# glassesBoard.net
KiCad netlist of a schematic drawn in EAGLE
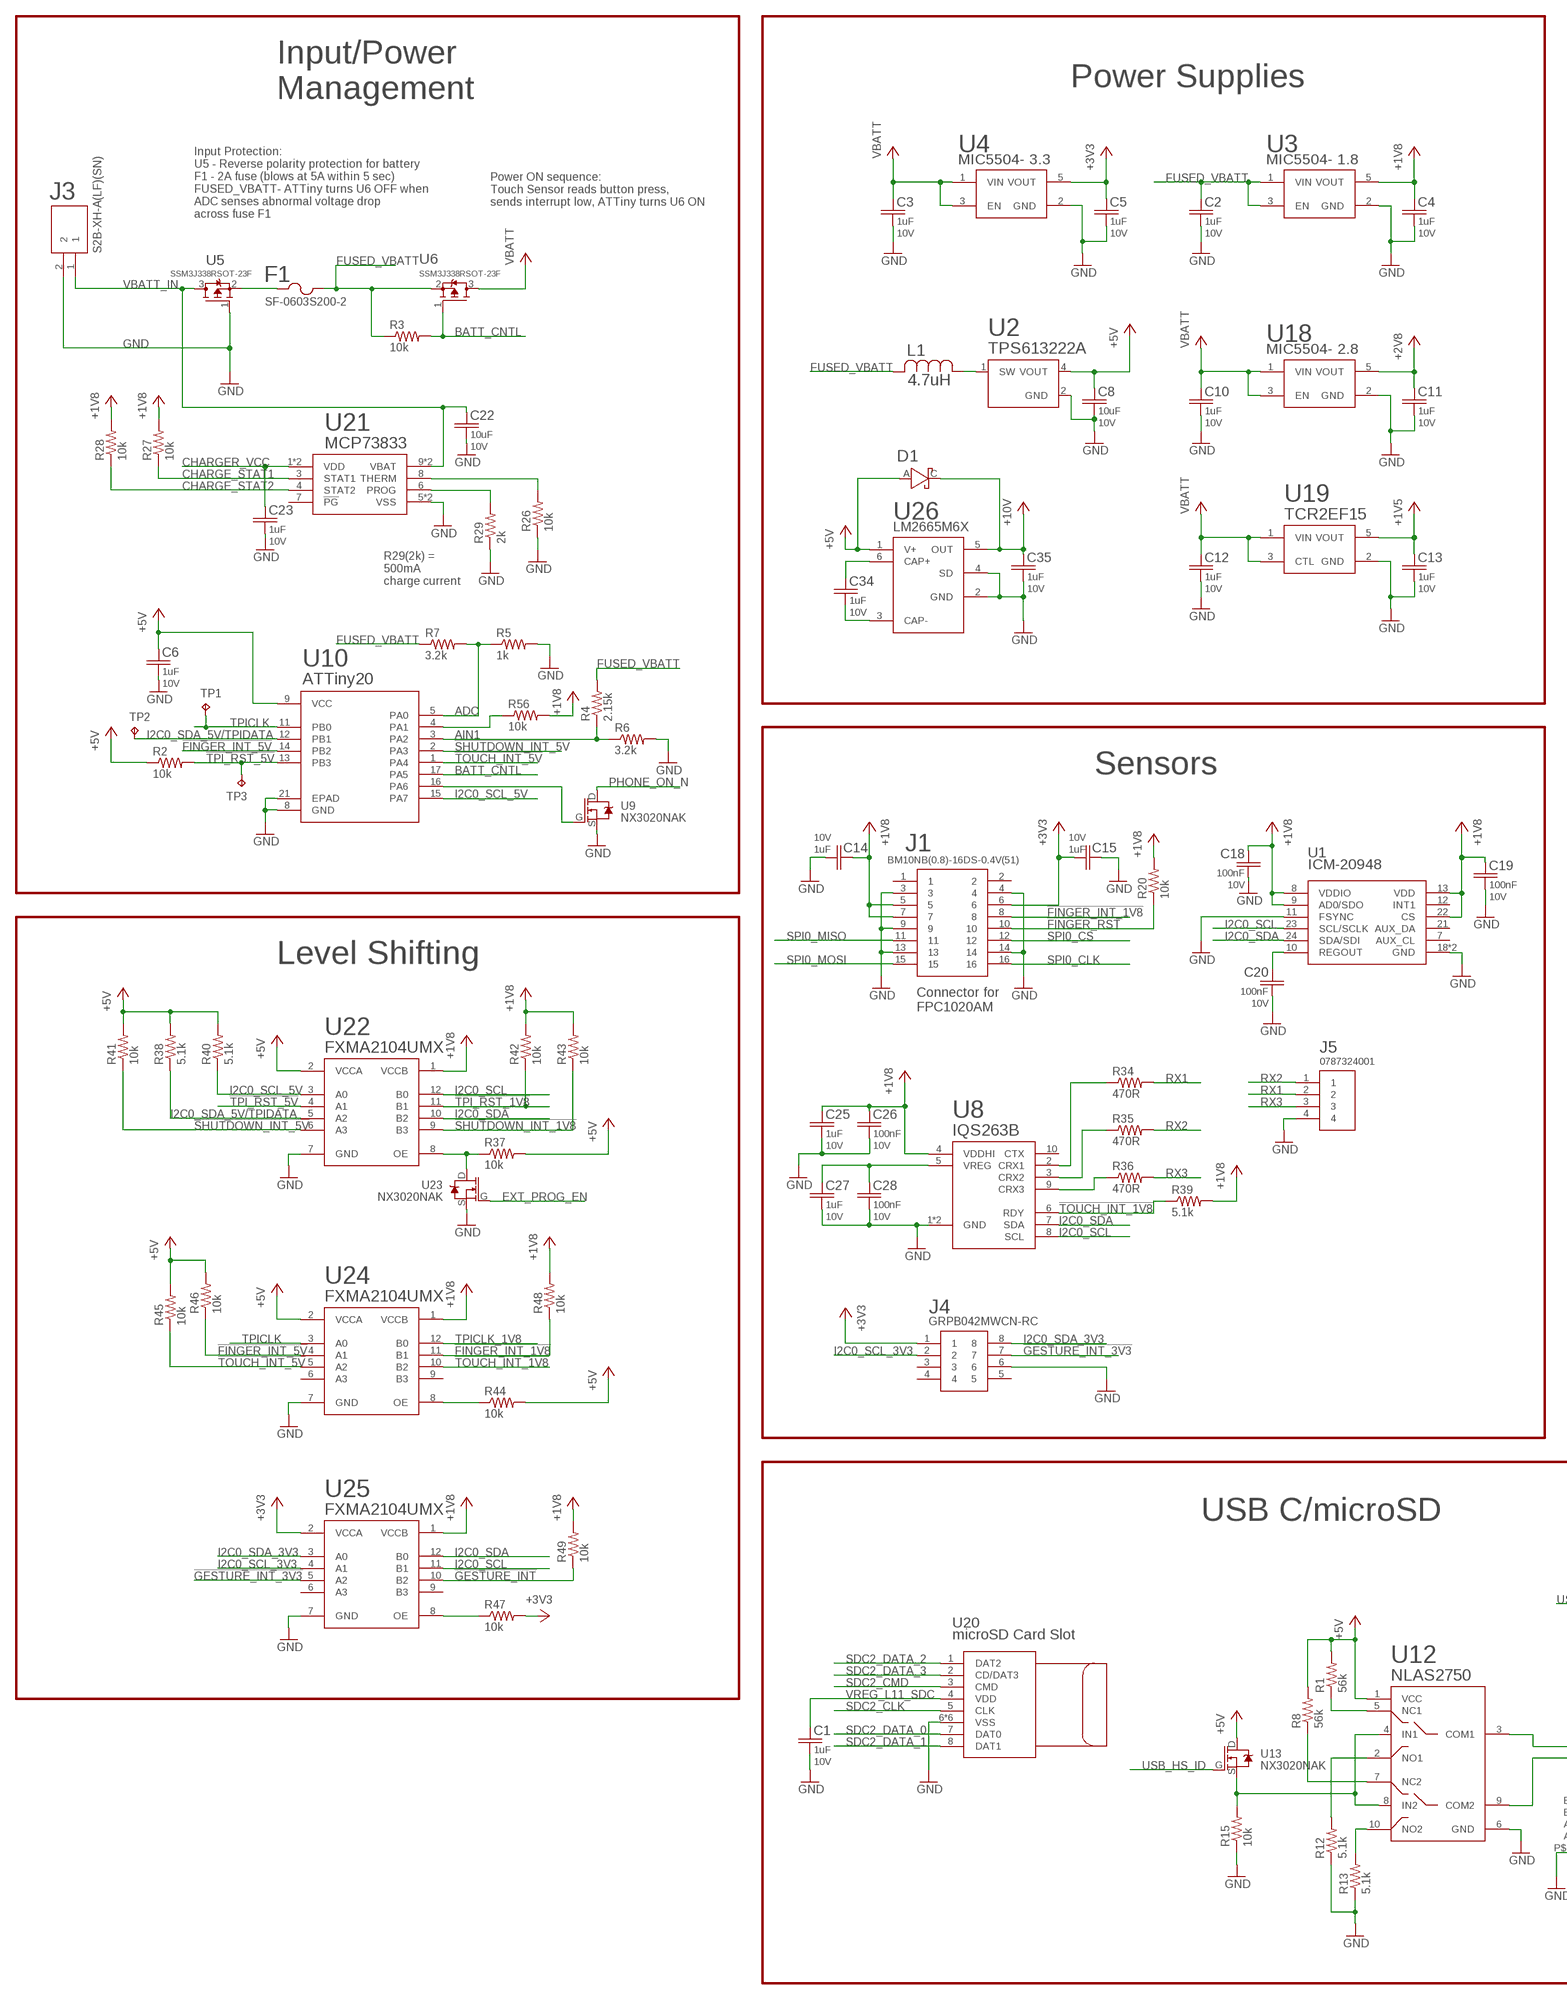
[diagram p0: schematic, sheet 1, part 1 of 2]
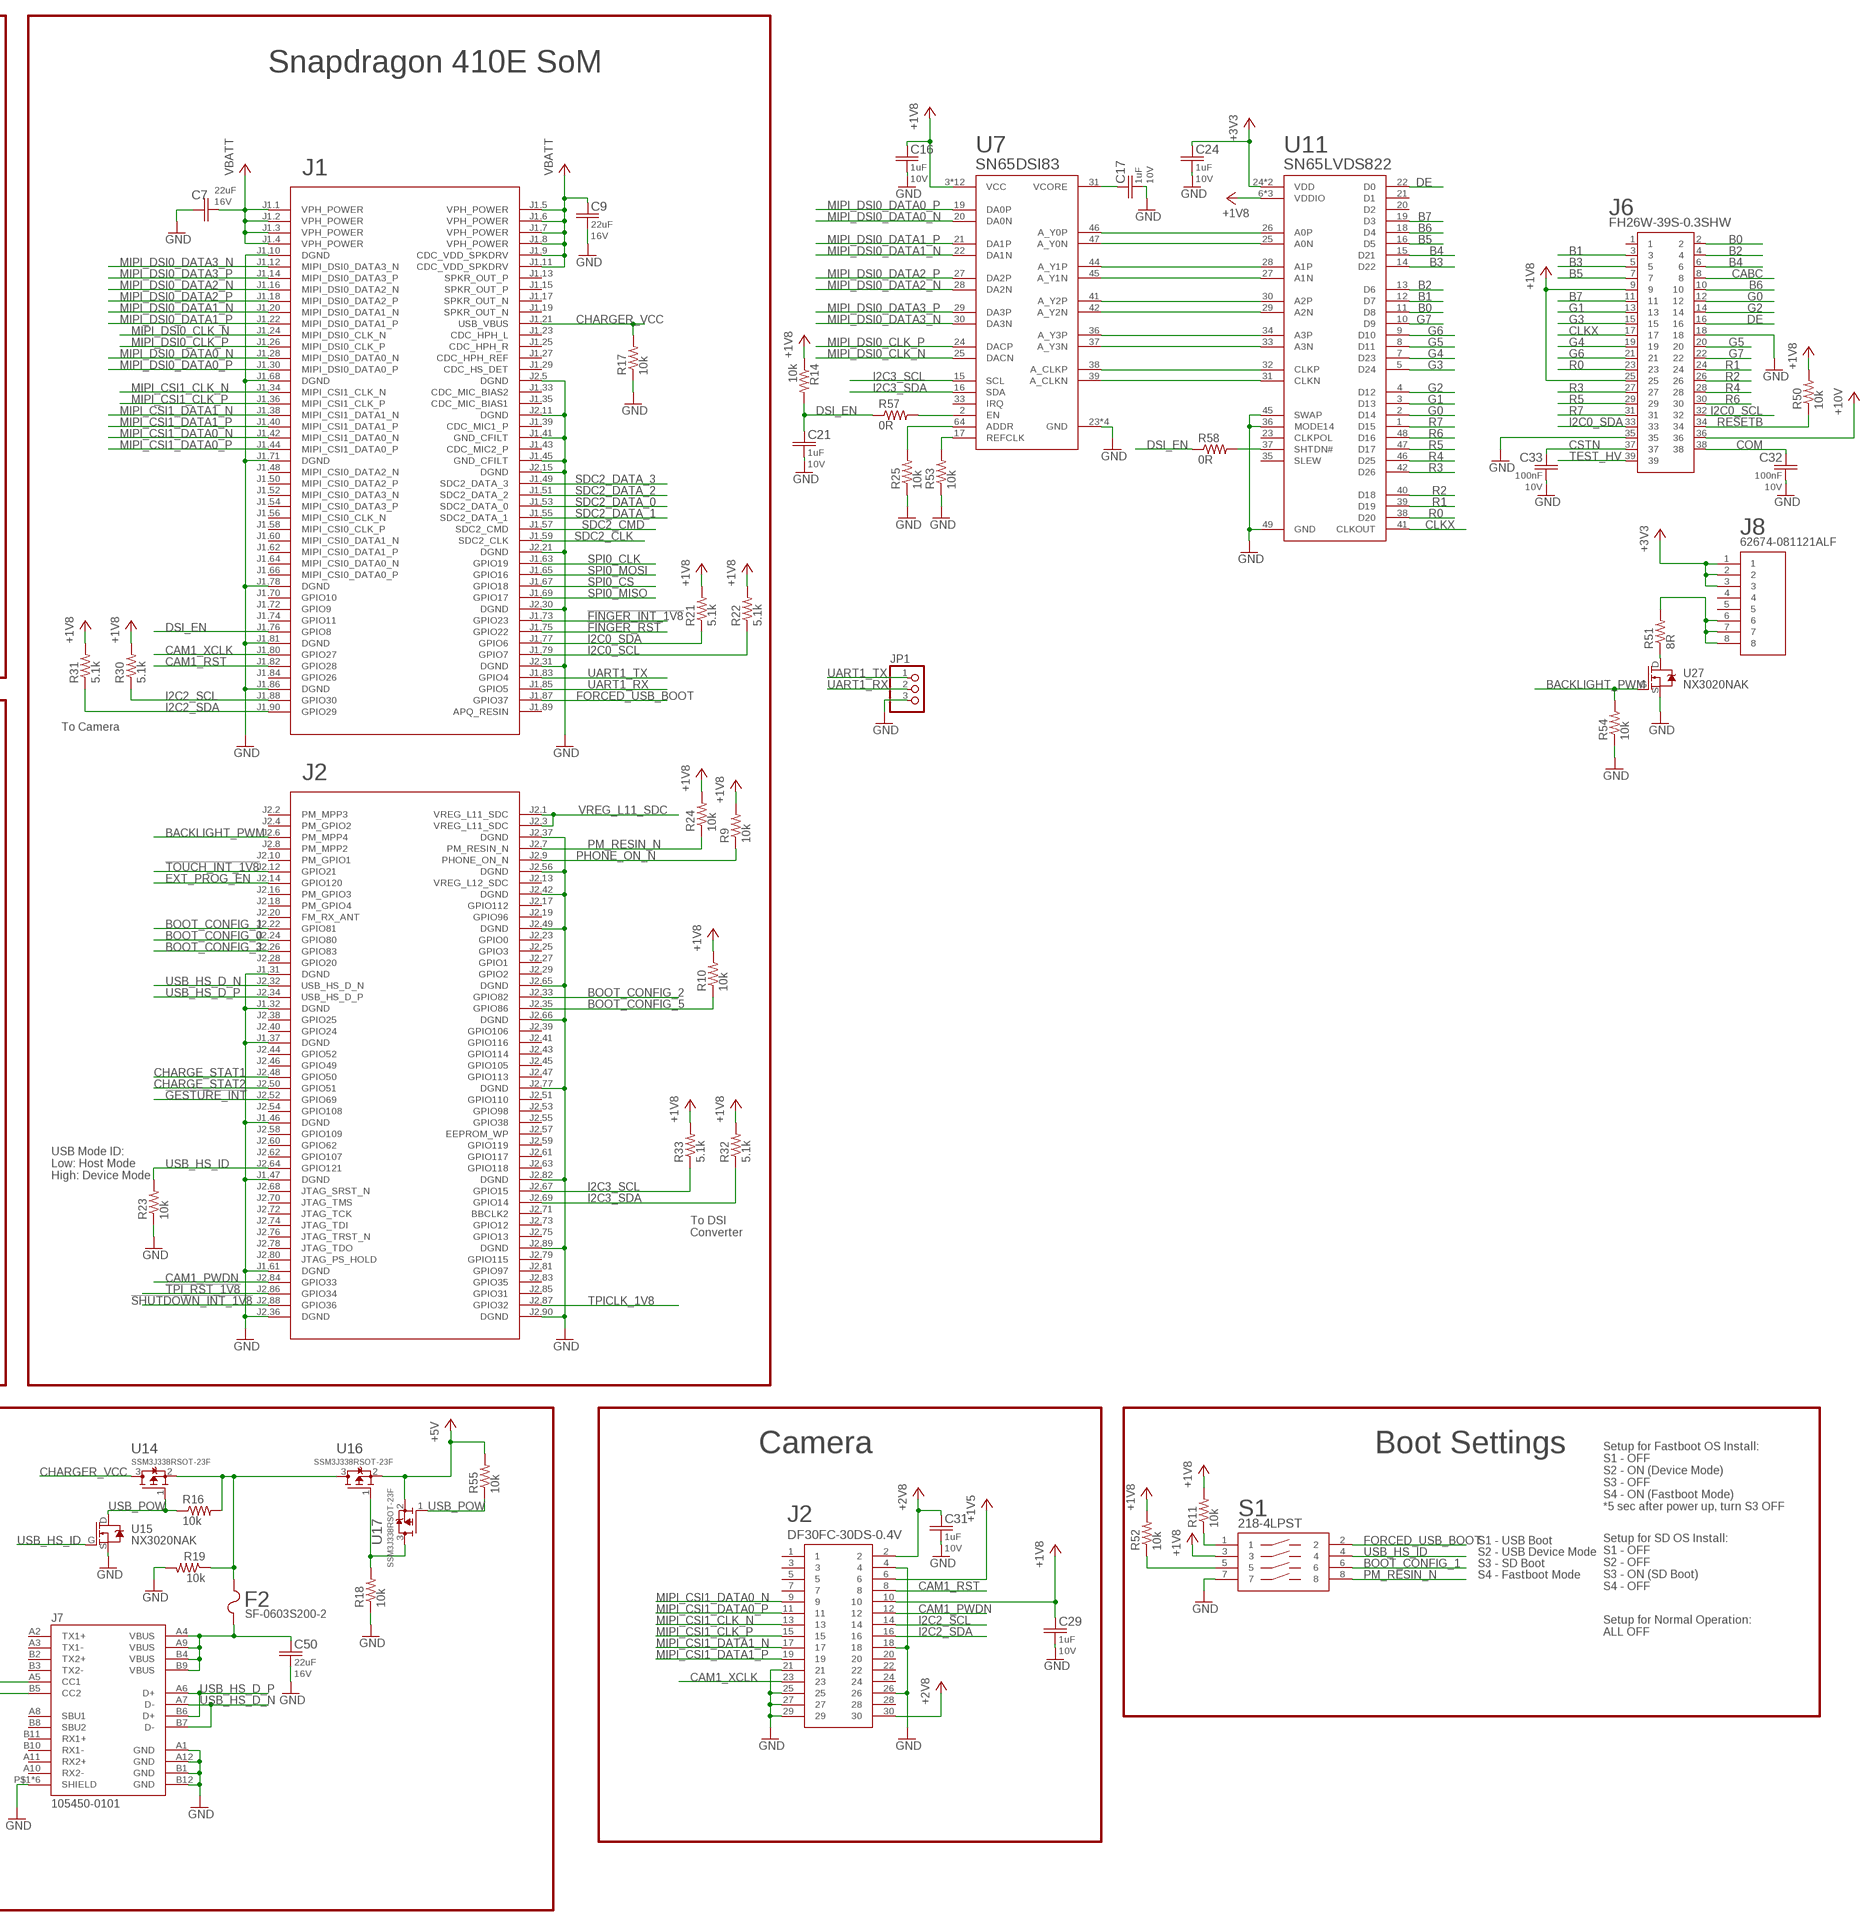
[diagram p1: schematic, sheet 1, part 2 of 2]

(export (version "E")
  (design (tool "Eeschema 10.0.6"))
  (components
    (comp (ref "C1")
      (value "1uF")
      (footprint "eagle-import:C0402")
      (fields (field (name "RATING") "10V"))
      (libsource (lib "eagle-import") (part "CL05A105MP5NNNC"))
    )
    (comp (ref "C2")
      (value "1uF")
      (footprint "eagle-import:C0402")
      (fields (field (name "RATING") "10V"))
      (libsource (lib "eagle-import") (part "CL05A105MP5NNNC"))
    )
    (comp (ref "C3")
      (value "1uF")
      (footprint "eagle-import:C0402")
      (fields (field (name "RATING") "10V"))
      (libsource (lib "eagle-import") (part "CL05A105MP5NNNC"))
    )
    (comp (ref "C4")
      (value "1uF")
      (footprint "eagle-import:C0402")
      (fields (field (name "RATING") "10V"))
      (libsource (lib "eagle-import") (part "CL05A105MP5NNNC"))
    )
    (comp (ref "C5")
      (value "1uF")
      (footprint "eagle-import:C0402")
      (fields (field (name "RATING") "10V"))
      (libsource (lib "eagle-import") (part "CL05A105MP5NNNC"))
    )
    (comp (ref "C6")
      (value "1uF")
      (footprint "eagle-import:C0402")
      (fields (field (name "RATING") "10V"))
      (libsource (lib "eagle-import") (part "CL05A105MP5NNNC"))
    )
    (comp (ref "C7")
      (value "22uF")
      (footprint "eagle-import:C0805")
      (fields (field (name "RATING") "16V"))
      (libsource (lib "eagle-import") (part "CL21A226MOCLRNC"))
    )
    (comp (ref "C8")
      (value "10uF")
      (footprint "eagle-import:C0603")
      (fields (field (name "RATING") "10V"))
      (libsource (lib "eagle-import") (part "GRM188R61A106KE69D"))
    )
    (comp (ref "C9")
      (value "22uF")
      (footprint "eagle-import:C0805")
      (fields (field (name "RATING") "16V"))
      (libsource (lib "eagle-import") (part "CL21A226MOCLRNC"))
    )
    (comp (ref "C10")
      (value "1uF")
      (footprint "eagle-import:C0402")
      (fields (field (name "RATING") "10V"))
      (libsource (lib "eagle-import") (part "CL05A105MP5NNNC"))
    )
    (comp (ref "C11")
      (value "1uF")
      (footprint "eagle-import:C0402")
      (fields (field (name "RATING") "10V"))
      (libsource (lib "eagle-import") (part "CL05A105MP5NNNC"))
    )
    (comp (ref "C12")
      (value "1uF")
      (footprint "eagle-import:C0402")
      (fields (field (name "RATING") "10V"))
      (libsource (lib "eagle-import") (part "CL05A105MP5NNNC"))
    )
    (comp (ref "C13")
      (value "1uF")
      (footprint "eagle-import:C0402")
      (fields (field (name "RATING") "10V"))
      (libsource (lib "eagle-import") (part "CL05A105MP5NNNC"))
    )
    (comp (ref "C14")
      (value "1uF")
      (footprint "eagle-import:C0402")
      (fields (field (name "RATING") "10V"))
      (libsource (lib "eagle-import") (part "CL05A105MP5NNNC"))
    )
    (comp (ref "C15")
      (value "1uF")
      (footprint "eagle-import:C0402")
      (fields (field (name "RATING") "10V"))
      (libsource (lib "eagle-import") (part "CL05A105MP5NNNC"))
    )
    (comp (ref "C16")
      (value "1uF")
      (footprint "eagle-import:C0402")
      (fields (field (name "RATING") "10V"))
      (libsource (lib "eagle-import") (part "CL05A105MP5NNNC"))
    )
    (comp (ref "C17")
      (value "1uF")
      (footprint "eagle-import:C0402")
      (fields (field (name "RATING") "10V"))
      (libsource (lib "eagle-import") (part "CL05A105MP5NNNC"))
    )
    (comp (ref "C18")
      (value "100nF")
      (footprint "eagle-import:C0402")
      (fields (field (name "RATING") "10V"))
      (libsource (lib "eagle-import") (part "CL05A104MP5NNNC"))
    )
    (comp (ref "C19")
      (value "100nF")
      (footprint "eagle-import:C0402")
      (fields (field (name "RATING") "10V"))
      (libsource (lib "eagle-import") (part "CL05A104MP5NNNC"))
    )
    (comp (ref "C20")
      (value "100nF")
      (footprint "eagle-import:C0402")
      (fields (field (name "RATING") "10V"))
      (libsource (lib "eagle-import") (part "CL05A104MP5NNNC"))
    )
    (comp (ref "C21")
      (value "1uF")
      (footprint "eagle-import:C0402")
      (fields (field (name "RATING") "10V"))
      (libsource (lib "eagle-import") (part "CL05A105MP5NNNC"))
    )
    (comp (ref "C22")
      (value "10uF")
      (footprint "eagle-import:C0603")
      (fields (field (name "RATING") "10V"))
      (libsource (lib "eagle-import") (part "GRM188R61A106KE69D"))
    )
    (comp (ref "C23")
      (value "1uF")
      (footprint "eagle-import:C0402")
      (fields (field (name "RATING") "10V"))
      (libsource (lib "eagle-import") (part "CL05A105MP5NNNC"))
    )
    (comp (ref "C24")
      (value "1uF")
      (footprint "eagle-import:C0402")
      (fields (field (name "RATING") "10V"))
      (libsource (lib "eagle-import") (part "CL05A105MP5NNNC"))
    )
    (comp (ref "C25")
      (value "1uF")
      (footprint "eagle-import:C0402")
      (fields (field (name "RATING") "10V"))
      (libsource (lib "eagle-import") (part "CL05A105MP5NNNC"))
    )
    (comp (ref "C26")
      (value "100nF")
      (footprint "eagle-import:C0402")
      (fields (field (name "RATING") "10V"))
      (libsource (lib "eagle-import") (part "CL05A104MP5NNNC"))
    )
    (comp (ref "C27")
      (value "1uF")
      (footprint "eagle-import:C0402")
      (fields (field (name "RATING") "10V"))
      (libsource (lib "eagle-import") (part "CL05A105MP5NNNC"))
    )
    (comp (ref "C28")
      (value "100nF")
      (footprint "eagle-import:C0402")
      (fields (field (name "RATING") "10V"))
      (libsource (lib "eagle-import") (part "CL05A104MP5NNNC"))
    )
    (comp (ref "C29")
      (value "1uF")
      (footprint "eagle-import:C0402")
      (fields (field (name "RATING") "10V"))
      (libsource (lib "eagle-import") (part "CL05A105MP5NNNC"))
    )
    (comp (ref "C31")
      (value "1uF")
      (footprint "eagle-import:C0402")
      (fields (field (name "RATING") "10V"))
      (libsource (lib "eagle-import") (part "CL05A105MP5NNNC"))
    )
    (comp (ref "C32")
      (value "100nF")
      (footprint "eagle-import:C0402")
      (fields (field (name "RATING") "10V"))
      (libsource (lib "eagle-import") (part "CL05A104MP5NNNC"))
    )
    (comp (ref "C33")
      (value "100nF")
      (footprint "eagle-import:C0402")
      (fields (field (name "RATING") "10V"))
      (libsource (lib "eagle-import") (part "CL05A104MP5NNNC"))
    )
    (comp (ref "C34")
      (value "1uF")
      (footprint "eagle-import:C0402")
      (fields (field (name "RATING") "10V"))
      (libsource (lib "eagle-import") (part "CL05A105MP5NNNC"))
    )
    (comp (ref "C35")
      (value "1uF")
      (footprint "eagle-import:C0402")
      (fields (field (name "RATING") "10V"))
      (libsource (lib "eagle-import") (part "CL05A105MP5NNNC"))
    )
    (comp (ref "C50")
      (value "22uF")
      (footprint "eagle-import:C0805")
      (fields (field (name "RATING") "16V"))
      (libsource (lib "eagle-import") (part "CL21A226MOCLRNC"))
    )
    (comp (ref "D1")
      (value "SDM03U40-7SC79")
      (footprint "eagle-import:SOD1608X70")
      (libsource (lib "eagle-import") (part "SDM03U40-7SC79"))
    )
    (comp (ref "F1")
      (value "SF-0603S200-2")
      (footprint "eagle-import:R0603")
      (libsource (lib "eagle-import") (part "SF-0603S200-2"))
    )
    (comp (ref "F2")
      (value "SF-0603S200-2")
      (footprint "eagle-import:R0603")
      (libsource (lib "eagle-import") (part "SF-0603S200-2"))
    )
    (comp (ref "J1")
      (value "BM10NB(0.8)-16DS-0.4V(51)")
      (footprint "eagle-import:BM10NB(0.8)-16DS-0.4V(51)")
      (libsource (lib "eagle-import") (part "BM10NB(0.8)-16DS-0.4V(51)"))
    )
    (comp (ref "J2")
      (value "DF30FC-30DS-0.4V")
      (footprint "eagle-import:DF30FC-30DS-0.4V")
      (libsource (lib "eagle-import") (part "DF30FC-30DS-0.4V"))
    )
    (comp (ref "J3")
      (value "S2B-XH-A(LF)(SN)")
      (footprint "eagle-import:S2B-XH-A(LF)(SN)")
      (libsource (lib "eagle-import") (part "S2B-XH-A(LF)(SN)"))
    )
    (comp (ref "J4")
      (value "GRPB042MWCN-RC")
      (footprint "eagle-import:GRPB042MWCN-RC")
      (libsource (lib "eagle-import") (part "GRPB042MWCN-RC"))
    )
    (comp (ref "J5")
      (value "0787324001")
      (footprint "eagle-import:0787324001")
      (libsource (lib "eagle-import") (part "0787324001"))
    )
    (comp (ref "J6")
      (value "FH26W-39S-0.3SHW")
      (footprint "eagle-import:FH26W-39S-0.3SHW")
      (libsource (lib "eagle-import") (part "FH26W-39S-0.3SHW"))
    )
    (comp (ref "J7")
      (value "105450-0101")
      (footprint "eagle-import:MOLEX_105450-0101")
      (fields
        (field (name "DIGI-KEY_PART_NUMBER") "WM12856CT-ND")
        (field (name "MF") "Molex")
        (field (name "MP") "1054500101")
      )
      (libsource (lib "eagle-import") (part "105450-0101"))
    )
    (comp (ref "J8")
      (value "62674-081121ALF")
      (footprint "eagle-import:62674-081121ALF")
      (libsource (lib "eagle-import") (part "62674-081121ALF"))
    )
    (comp (ref "JP1")
      (value "PINHD-1X3/90")
      (footprint "eagle-import:1X03_90")
      (libsource (lib "eagle-import") (part "PINHD-1X3/90"))
    )
    (comp (ref "L1")
      (value "4.7uH")
      (footprint "eagle-import:1008")
      (libsource (lib "eagle-import") (part "DFE252012P-4R7M=P2{dblquote}"))
    )
    (comp (ref "R1")
      (value "56k")
      (footprint "eagle-import:R0402")
      (libsource (lib "eagle-import") (part "RC0402JR-0756KL"))
    )
    (comp (ref "R2")
      (value "10k")
      (footprint "eagle-import:R0402")
      (libsource (lib "eagle-import") (part "RC0402JR-0710KL"))
    )
    (comp (ref "R3")
      (value "10k")
      (footprint "eagle-import:R0402")
      (libsource (lib "eagle-import") (part "RC0402JR-0710KL"))
    )
    (comp (ref "R4")
      (value "2.15k")
      (footprint "eagle-import:R0402")
      (libsource (lib "eagle-import") (part "RC0402FR-072K15L"))
    )
    (comp (ref "R5")
      (value "1k")
      (footprint "eagle-import:R0402")
      (libsource (lib "eagle-import") (part "RC0402FR-071KL"))
    )
    (comp (ref "R6")
      (value "3.2k")
      (footprint "eagle-import:R0402")
      (libsource (lib "eagle-import") (part "RT0402DRE073K2L"))
    )
    (comp (ref "R7")
      (value "3.2k")
      (footprint "eagle-import:R0402")
      (libsource (lib "eagle-import") (part "RT0402DRE073K2L"))
    )
    (comp (ref "R8")
      (value "56k")
      (footprint "eagle-import:R0402")
      (libsource (lib "eagle-import") (part "RC0402JR-0756KL"))
    )
    (comp (ref "R9")
      (value "10k")
      (footprint "eagle-import:R0402")
      (libsource (lib "eagle-import") (part "RC0402JR-0710KL"))
    )
    (comp (ref "R10")
      (value "10k")
      (footprint "eagle-import:R0402")
      (libsource (lib "eagle-import") (part "RC0402JR-0710KL"))
    )
    (comp (ref "R11")
      (value "10k")
      (footprint "eagle-import:R0402")
      (libsource (lib "eagle-import") (part "RC0402JR-0710KL"))
    )
    (comp (ref "R12")
      (value "5.1k")
      (footprint "eagle-import:R0402")
      (libsource (lib "eagle-import") (part "RC0402JR-075K1L"))
    )
    (comp (ref "R13")
      (value "5.1k")
      (footprint "eagle-import:R0402")
      (libsource (lib "eagle-import") (part "RC0402JR-075K1L"))
    )
    (comp (ref "R14")
      (value "10k")
      (footprint "eagle-import:R0402")
      (libsource (lib "eagle-import") (part "RC0402JR-0710KL"))
    )
    (comp (ref "R15")
      (value "10k")
      (footprint "eagle-import:R0402")
      (libsource (lib "eagle-import") (part "RC0402JR-0710KL"))
    )
    (comp (ref "R16")
      (value "10k")
      (footprint "eagle-import:R0402")
      (libsource (lib "eagle-import") (part "RC0402JR-0710KL"))
    )
    (comp (ref "R17")
      (value "10k")
      (footprint "eagle-import:R0402")
      (libsource (lib "eagle-import") (part "RC0402JR-0710KL"))
    )
    (comp (ref "R18")
      (value "10k")
      (footprint "eagle-import:R0402")
      (libsource (lib "eagle-import") (part "RC0402JR-0710KL"))
    )
    (comp (ref "R19")
      (value "10k")
      (footprint "eagle-import:R0402")
      (libsource (lib "eagle-import") (part "RC0402JR-0710KL"))
    )
    (comp (ref "R20")
      (value "10k")
      (footprint "eagle-import:R0402")
      (libsource (lib "eagle-import") (part "RC0402JR-0710KL"))
    )
    (comp (ref "R21")
      (value "5.1k")
      (footprint "eagle-import:R0402")
      (libsource (lib "eagle-import") (part "RC0402JR-075K1L"))
    )
    (comp (ref "R22")
      (value "5.1k")
      (footprint "eagle-import:R0402")
      (libsource (lib "eagle-import") (part "RC0402JR-075K1L"))
    )
    (comp (ref "R23")
      (value "10k")
      (footprint "eagle-import:R0402")
      (libsource (lib "eagle-import") (part "RC0402JR-0710KL"))
    )
    (comp (ref "R24")
      (value "10k")
      (footprint "eagle-import:R0402")
      (libsource (lib "eagle-import") (part "RC0402JR-0710KL"))
    )
    (comp (ref "R25")
      (value "10k")
      (footprint "eagle-import:R0402")
      (libsource (lib "eagle-import") (part "RC0402JR-0710KL"))
    )
    (comp (ref "R26")
      (value "10k")
      (footprint "eagle-import:R0402")
      (libsource (lib "eagle-import") (part "RC0402JR-0710KL"))
    )
    (comp (ref "R27")
      (value "10k")
      (footprint "eagle-import:R0402")
      (libsource (lib "eagle-import") (part "RC0402JR-0710KL"))
    )
    (comp (ref "R28")
      (value "10k")
      (footprint "eagle-import:R0402")
      (libsource (lib "eagle-import") (part "RC0402JR-0710KL"))
    )
    (comp (ref "R29")
      (value "2k")
      (footprint "eagle-import:R0402")
      (libsource (lib "eagle-import") (part "RC0402FR-072KL"))
    )
    (comp (ref "R30")
      (value "5.1k")
      (footprint "eagle-import:R0402")
      (libsource (lib "eagle-import") (part "RC0402JR-075K1L"))
    )
    (comp (ref "R31")
      (value "5.1k")
      (footprint "eagle-import:R0402")
      (libsource (lib "eagle-import") (part "RC0402JR-075K1L"))
    )
    (comp (ref "R32")
      (value "5.1k")
      (footprint "eagle-import:R0402")
      (libsource (lib "eagle-import") (part "RC0402JR-075K1L"))
    )
    (comp (ref "R33")
      (value "5.1k")
      (footprint "eagle-import:R0402")
      (libsource (lib "eagle-import") (part "RC0402JR-075K1L"))
    )
    (comp (ref "R34")
      (value "470R")
      (footprint "eagle-import:R0402")
      (libsource (lib "eagle-import") (part "RC0402JR-07470RL"))
    )
    (comp (ref "R35")
      (value "470R")
      (footprint "eagle-import:R0402")
      (libsource (lib "eagle-import") (part "RC0402JR-07470RL"))
    )
    (comp (ref "R36")
      (value "470R")
      (footprint "eagle-import:R0402")
      (libsource (lib "eagle-import") (part "RC0402JR-07470RL"))
    )
    (comp (ref "R37")
      (value "10k")
      (footprint "eagle-import:R0402")
      (libsource (lib "eagle-import") (part "RC0402JR-0710KL"))
    )
    (comp (ref "R38")
      (value "5.1k")
      (footprint "eagle-import:R0402")
      (libsource (lib "eagle-import") (part "RC0402JR-075K1L"))
    )
    (comp (ref "R39")
      (value "5.1k")
      (footprint "eagle-import:R0402")
      (libsource (lib "eagle-import") (part "RC0402JR-075K1L"))
    )
    (comp (ref "R40")
      (value "5.1k")
      (footprint "eagle-import:R0402")
      (libsource (lib "eagle-import") (part "RC0402JR-075K1L"))
    )
    (comp (ref "R41")
      (value "10k")
      (footprint "eagle-import:R0402")
      (libsource (lib "eagle-import") (part "RC0402JR-0710KL"))
    )
    (comp (ref "R42")
      (value "10k")
      (footprint "eagle-import:R0402")
      (libsource (lib "eagle-import") (part "RC0402JR-0710KL"))
    )
    (comp (ref "R43")
      (value "10k")
      (footprint "eagle-import:R0402")
      (libsource (lib "eagle-import") (part "RC0402JR-0710KL"))
    )
    (comp (ref "R44")
      (value "10k")
      (footprint "eagle-import:R0402")
      (libsource (lib "eagle-import") (part "RC0402JR-0710KL"))
    )
    (comp (ref "R45")
      (value "10k")
      (footprint "eagle-import:R0402")
      (libsource (lib "eagle-import") (part "RC0402JR-0710KL"))
    )
    (comp (ref "R46")
      (value "10k")
      (footprint "eagle-import:R0402")
      (libsource (lib "eagle-import") (part "RC0402JR-0710KL"))
    )
    (comp (ref "R47")
      (value "10k")
      (footprint "eagle-import:R0402")
      (libsource (lib "eagle-import") (part "RC0402JR-0710KL"))
    )
    (comp (ref "R48")
      (value "10k")
      (footprint "eagle-import:R0402")
      (libsource (lib "eagle-import") (part "RC0402JR-0710KL"))
    )
    (comp (ref "R49")
      (value "10k")
      (footprint "eagle-import:R0402")
      (libsource (lib "eagle-import") (part "RC0402JR-0710KL"))
    )
    (comp (ref "R50")
      (value "10k")
      (footprint "eagle-import:R0402")
      (libsource (lib "eagle-import") (part "RC0402JR-0710KL"))
    )
    (comp (ref "R51")
      (value "8R")
      (footprint "eagle-import:R0402")
      (libsource (lib "eagle-import") (part "RMCF0402JT8R20"))
    )
    (comp (ref "R52")
      (value "10k")
      (footprint "eagle-import:R0402")
      (libsource (lib "eagle-import") (part "RC0402JR-0710KL"))
    )
    (comp (ref "R53")
      (value "10k")
      (footprint "eagle-import:R0402")
      (libsource (lib "eagle-import") (part "RC0402JR-0710KL"))
    )
    (comp (ref "R54")
      (value "10k")
      (footprint "eagle-import:R0402")
      (libsource (lib "eagle-import") (part "RC0402JR-0710KL"))
    )
    (comp (ref "R55")
      (value "10k")
      (footprint "eagle-import:R0402")
      (libsource (lib "eagle-import") (part "RC0402JR-0710KL"))
    )
    (comp (ref "R56")
      (value "10k")
      (footprint "eagle-import:R0402")
      (libsource (lib "eagle-import") (part "RC0402JR-0710KL"))
    )
    (comp (ref "R57")
      (value "0R")
      (footprint "eagle-import:R0402")
      (libsource (lib "eagle-import") (part "RC0402JR-0710KL"))
    )
    (comp (ref "R58")
      (value "0R")
      (footprint "eagle-import:R0402")
      (libsource (lib "eagle-import") (part "RC0402JR-0710KL"))
    )
    (comp (ref "S1")
      (value "218-4LPST")
      (footprint "eagle-import:218-4LPST")
      (libsource (lib "eagle-import") (part "218-4LPST"))
    )
    (comp (ref "TP1")
      (value "TPB2,54")
      (footprint "eagle-import:B2,54")
      (libsource (lib "eagle-import") (part "TPB2,54"))
    )
    (comp (ref "TP2")
      (value "TPB2,54")
      (footprint "eagle-import:B2,54")
      (libsource (lib "eagle-import") (part "TPB2,54"))
    )
    (comp (ref "TP3")
      (value "TPB2,54")
      (footprint "eagle-import:B2,54")
      (libsource (lib "eagle-import") (part "TPB2,54"))
    )
    (comp (ref "U$1")
      (value "DART-SD410")
      (footprint "eagle-import:DART-SD410")
      (libsource (lib "eagle-import") (part "DART-SD410"))
    )
    (comp (ref "U1")
      (value "ICM-20948")
      (footprint "eagle-import:QFN40P300X300X105-25N")
      (libsource (lib "eagle-import") (part "ICM-20948"))
    )
    (comp (ref "U2")
      (value "TPS613222A")
      (footprint "eagle-import:SOT23-5")
      (libsource (lib "eagle-import") (part "TPS613222A"))
    )
    (comp (ref "U3")
      (value "1.8")
      (footprint "eagle-import:SOT23-5")
      (libsource (lib "eagle-import") (part "MIC5504-1.8SOT23-5"))
    )
    (comp (ref "U4")
      (value "3.3")
      (footprint "eagle-import:SOT23-5")
      (libsource (lib "eagle-import") (part "MIC5504-3.3"))
    )
    (comp (ref "U5")
      (value "SSM3J338RSOT-23F")
      (footprint "eagle-import:SOTFL95P240X80-3")
      (libsource (lib "eagle-import") (part "SSM3J338RSOT-23F"))
    )
    (comp (ref "U6")
      (value "SSM3J338RSOT-23F")
      (footprint "eagle-import:SOTFL95P240X80-3")
      (libsource (lib "eagle-import") (part "SSM3J338RSOT-23F"))
    )
    (comp (ref "U7")
      (value "SN65DSI83-Q1S-PQFP-G64")
      (footprint "eagle-import:QFP50P1200X1200X120-65T300")
      (libsource (lib "eagle-import") (part "SN65DSI83-Q1S-PQFP-G64"))
    )
    (comp (ref "U8")
      (value "IQS263BDFN10")
      (footprint "eagle-import:DFN10-3X3")
      (libsource (lib "eagle-import") (part "IQS263BDFN10"))
    )
    (comp (ref "U9")
      (value "NX3020NAK")
      (footprint "eagle-import:SOT-23_(TO-236AB)")
      (fields (field (name "PART#") "NX3020NAK"))
      (libsource (lib "eagle-import") (part "NX3020NAK"))
    )
    (comp (ref "U10")
      (value "ATTINY20-MMH")
      (footprint "eagle-import:20M2")
      (fields (field (name "MANUFACTURER_PART_NUMBER") "ATTINY20MMH"))
      (libsource (lib "eagle-import") (part "ATTINY20-MMH"))
    )
    (comp (ref "U11")
      (value "SN65LVDS822VQFN48")
      (footprint "eagle-import:QFN50P700X700X100-49T515")
      (libsource (lib "eagle-import") (part "SN65LVDS822VQFN48"))
    )
    (comp (ref "U12")
      (value "NLAS2750")
      (footprint "eagle-import:UQFN10")
      (libsource (lib "eagle-import") (part "NLAS2750"))
    )
    (comp (ref "U13")
      (value "NX3020NAK")
      (footprint "eagle-import:SOT-23_(TO-236AB)")
      (fields (field (name "PART#") "NX3020NAK"))
      (libsource (lib "eagle-import") (part "NX3020NAK"))
    )
    (comp (ref "U14")
      (value "SSM3J338RSOT-23F")
      (footprint "eagle-import:SOTFL95P240X80-3")
      (libsource (lib "eagle-import") (part "SSM3J338RSOT-23F"))
    )
    (comp (ref "U15")
      (value "NX3020NAK")
      (footprint "eagle-import:SOT-23_(TO-236AB)")
      (fields (field (name "PART#") "NX3020NAK"))
      (libsource (lib "eagle-import") (part "NX3020NAK"))
    )
    (comp (ref "U16")
      (value "SSM3J338RSOT-23F")
      (footprint "eagle-import:SOTFL95P240X80-3")
      (libsource (lib "eagle-import") (part "SSM3J338RSOT-23F"))
    )
    (comp (ref "U17")
      (value "SSM3J338RSOT-23F")
      (footprint "eagle-import:SOTFL95P240X80-3")
      (libsource (lib "eagle-import") (part "SSM3J338RSOT-23F"))
    )
    (comp (ref "U18")
      (value "2.8")
      (footprint "eagle-import:SOT23-5")
      (libsource (lib "eagle-import") (part "MIC5504-2.8"))
    )
    (comp (ref "U19")
      (value "TCR2EF15SOT-25")
      (footprint "eagle-import:SOT95P275X130-5")
      (libsource (lib "eagle-import") (part "TCR2EF15SOT-25"))
    )
    (comp (ref "U20")
      (value "MICROSD")
      (footprint "eagle-import:MICROSD")
      (libsource (lib "eagle-import") (part "MICROSD"))
    )
    (comp (ref "U21")
      (value "MCP73833")
      (footprint "eagle-import:DFN10-3X3")
      (libsource (lib "eagle-import") (part "MCP73833"))
    )
    (comp (ref "U22")
      (value "FXMA2104UMX")
      (footprint "eagle-import:12MLP")
      (libsource (lib "eagle-import") (part "FXMA2104UMX"))
    )
    (comp (ref "U23")
      (value "NX3020NAK")
      (footprint "eagle-import:SOT-23_(TO-236AB)")
      (fields (field (name "PART#") "NX3020NAK"))
      (libsource (lib "eagle-import") (part "NX3020NAK"))
    )
    (comp (ref "U24")
      (value "FXMA2104UMX")
      (footprint "eagle-import:12MLP")
      (libsource (lib "eagle-import") (part "FXMA2104UMX"))
    )
    (comp (ref "U25")
      (value "FXMA2104UMX")
      (footprint "eagle-import:12MLP")
      (libsource (lib "eagle-import") (part "FXMA2104UMX"))
    )
    (comp (ref "U26")
      (value "LM2665M6XSOT23-6")
      (footprint "eagle-import:SOT95P280X145-6")
      (libsource (lib "eagle-import") (part "LM2665M6XSOT23-6"))
    )
    (comp (ref "U27")
      (value "NX3020NAK")
      (footprint "eagle-import:SOT-23_(TO-236AB)")
      (fields (field (name "PART#") "NX3020NAK"))
      (libsource (lib "eagle-import") (part "NX3020NAK"))
    )
  )
  (nets
    (net (code "1") (name "+1V5") (class "Default")
      (node (ref "C13") (pin "1") (pinfunction "1_1") (pintype "bidirectional"))
      (node (ref "J2") (pin "6") (pinfunction "6_6") (pintype "bidirectional"))
      (node (ref "U19") (pin "5") (pinfunction "VOUT_5") (pintype "bidirectional"))
    )
    (net (code "2") (name "+1V8") (class "Default")
      (node (ref "C14") (pin "1") (pinfunction "1_1") (pintype "bidirectional"))
      (node (ref "C16") (pin "1") (pinfunction "1_1") (pintype "bidirectional"))
      (node (ref "C18") (pin "1") (pinfunction "1_1") (pintype "bidirectional"))
      (node (ref "C19") (pin "1") (pinfunction "1_1") (pintype "bidirectional"))
      (node (ref "C25") (pin "1") (pinfunction "1_1") (pintype "bidirectional"))
      (node (ref "C26") (pin "1") (pinfunction "1_1") (pintype "bidirectional"))
      (node (ref "C29") (pin "1") (pinfunction "1_1") (pintype "bidirectional"))
      (node (ref "C4") (pin "1") (pinfunction "1_1") (pintype "bidirectional"))
      (node (ref "J1") (pin "5") (pinfunction "5_5") (pintype "bidirectional"))
      (node (ref "J1") (pin "7") (pinfunction "7_7") (pintype "bidirectional"))
      (node (ref "J2") (pin "10") (pinfunction "10_10") (pintype "bidirectional"))
      (node (ref "J6") (pin "25") (pinfunction "25_25") (pintype "bidirectional"))
      (node (ref "J6") (pin "9") (pinfunction "9_9") (pintype "bidirectional"))
      (node (ref "R10") (pin "2") (pinfunction "2_2") (pintype "passive"))
      (node (ref "R11") (pin "2") (pinfunction "2_2") (pintype "passive"))
      (node (ref "R14") (pin "1") (pinfunction "1_1") (pintype "passive"))
      (node (ref "R20") (pin "2") (pinfunction "2_2") (pintype "passive"))
      (node (ref "R21") (pin "2") (pinfunction "2_2") (pintype "passive"))
      (node (ref "R22") (pin "2") (pinfunction "2_2") (pintype "passive"))
      (node (ref "R24") (pin "2") (pinfunction "2_2") (pintype "passive"))
      (node (ref "R27") (pin "2") (pinfunction "2_2") (pintype "passive"))
      (node (ref "R28") (pin "2") (pinfunction "2_2") (pintype "passive"))
      (node (ref "R30") (pin "2") (pinfunction "2_2") (pintype "passive"))
      (node (ref "R31") (pin "2") (pinfunction "2_2") (pintype "passive"))
      (node (ref "R32") (pin "2") (pinfunction "2_2") (pintype "passive"))
      (node (ref "R33") (pin "2") (pinfunction "2_2") (pintype "passive"))
      (node (ref "R39") (pin "2") (pinfunction "2_2") (pintype "passive"))
      (node (ref "R42") (pin "2") (pinfunction "2_2") (pintype "passive"))
      (node (ref "R43") (pin "2") (pinfunction "2_2") (pintype "passive"))
      (node (ref "R48") (pin "2") (pinfunction "2_2") (pintype "passive"))
      (node (ref "R49") (pin "2") (pinfunction "2_2") (pintype "passive"))
      (node (ref "R50") (pin "2") (pinfunction "2_2") (pintype "passive"))
      (node (ref "R52") (pin "2") (pinfunction "2_2") (pintype "passive"))
      (node (ref "R56") (pin "2") (pinfunction "2_2") (pintype "passive"))
      (node (ref "R9") (pin "2") (pinfunction "2_2") (pintype "passive"))
      (node (ref "S1") (pin "3") (pinfunction "3_3") (pintype "bidirectional"))
      (node (ref "U1") (pin "13") (pinfunction "VDD_13") (pintype "bidirectional"))
      (node (ref "U1") (pin "22") (pinfunction "CS_22") (pintype "bidirectional"))
      (node (ref "U1") (pin "8") (pinfunction "VDDIO_8") (pintype "bidirectional"))
      (node (ref "U1") (pin "9") (pinfunction "AD0/SDO_9") (pintype "bidirectional"))
      (node (ref "U11") (pin "17") (pinfunction "VDDIO_17") (pintype "bidirectional"))
      (node (ref "U11") (pin "43") (pinfunction "VDDIO_43") (pintype "bidirectional"))
      (node (ref "U11") (pin "6") (pinfunction "VDDIO_6") (pintype "bidirectional"))
      (node (ref "U22") (pin "1") (pinfunction "VCCB_1") (pintype "bidirectional"))
      (node (ref "U24") (pin "1") (pinfunction "VCCB_1") (pintype "bidirectional"))
      (node (ref "U25") (pin "1") (pinfunction "VCCB_1") (pintype "bidirectional"))
      (node (ref "U3") (pin "5") (pinfunction "VOUT_5") (pintype "bidirectional"))
      (node (ref "U7") (pin "14") (pinfunction "VCC_14") (pintype "bidirectional"))
      (node (ref "U7") (pin "18") (pinfunction "VCC_18") (pintype "bidirectional"))
      (node (ref "U7") (pin "3") (pinfunction "VCC_3") (pintype "bidirectional"))
      (node (ref "U7") (pin "32") (pinfunction "VCC_32") (pintype "bidirectional"))
      (node (ref "U7") (pin "35") (pinfunction "VCC_35") (pintype "bidirectional"))
      (node (ref "U7") (pin "40") (pinfunction "VCC_40") (pintype "bidirectional"))
      (node (ref "U7") (pin "43") (pinfunction "VCC_43") (pintype "bidirectional"))
      (node (ref "U7") (pin "48") (pinfunction "VCC_48") (pintype "bidirectional"))
      (node (ref "U7") (pin "49") (pinfunction "VCC_49") (pintype "bidirectional"))
      (node (ref "U7") (pin "55") (pinfunction "VCC_55") (pintype "bidirectional"))
      (node (ref "U7") (pin "58") (pinfunction "VCC_58") (pintype "bidirectional"))
      (node (ref "U7") (pin "63") (pinfunction "VCC_63") (pintype "bidirectional"))
      (node (ref "U8") (pin "4") (pinfunction "VDDHI_4") (pintype "bidirectional"))
    )
    (net (code "3") (name "+2V8") (class "Default")
      (node (ref "C11") (pin "1") (pinfunction "1_1") (pintype "bidirectional"))
      (node (ref "C31") (pin "1") (pinfunction "1_1") (pintype "bidirectional"))
      (node (ref "J2") (pin "2") (pinfunction "2_2") (pintype "bidirectional"))
      (node (ref "J2") (pin "30") (pinfunction "30_30") (pintype "bidirectional"))
      (node (ref "U18") (pin "5") (pinfunction "VOUT_5") (pintype "bidirectional"))
    )
    (net (code "4") (name "+3V3") (class "Default")
      (node (ref "C15") (pin "2") (pinfunction "2_2") (pintype "bidirectional"))
      (node (ref "C24") (pin "1") (pinfunction "1_1") (pintype "bidirectional"))
      (node (ref "C5") (pin "1") (pinfunction "1_1") (pintype "bidirectional"))
      (node (ref "J1") (pin "6") (pinfunction "6_6") (pintype "bidirectional"))
      (node (ref "J4") (pin "1") (pinfunction "1_1") (pintype "bidirectional"))
      (node (ref "J8") (pin "1") (pinfunction "1_1") (pintype "bidirectional"))
      (node (ref "J8") (pin "2") (pinfunction "2_2") (pintype "bidirectional"))
      (node (ref "J8") (pin "3") (pinfunction "3_3") (pintype "bidirectional"))
      (node (ref "R47") (pin "2") (pinfunction "2_2") (pintype "passive"))
      (node (ref "U11") (pin "24") (pinfunction "VDD_24") (pintype "bidirectional"))
      (node (ref "U11") (pin "44") (pinfunction "VDD_44") (pintype "bidirectional"))
      (node (ref "U25") (pin "2") (pinfunction "VCCA_2") (pintype "bidirectional"))
      (node (ref "U4") (pin "5") (pinfunction "VOUT_5") (pintype "bidirectional"))
    )
    (net (code "5") (name "+5V") (class "Default")
      (node (ref "C6") (pin "1") (pinfunction "1_1") (pintype "bidirectional"))
      (node (ref "C8") (pin "1") (pinfunction "1_1") (pintype "bidirectional"))
      (node (ref "D1") (pin "A") (pinfunction "A_A") (pintype "bidirectional"))
      (node (ref "R1") (pin "2") (pinfunction "2_2") (pintype "passive"))
      (node (ref "R2") (pin "1") (pinfunction "1_1") (pintype "passive"))
      (node (ref "R37") (pin "2") (pinfunction "2_2") (pintype "passive"))
      (node (ref "R38") (pin "2") (pinfunction "2_2") (pintype "passive"))
      (node (ref "R40") (pin "2") (pinfunction "2_2") (pintype "passive"))
      (node (ref "R41") (pin "2") (pinfunction "2_2") (pintype "passive"))
      (node (ref "R44") (pin "2") (pinfunction "2_2") (pintype "passive"))
      (node (ref "R45") (pin "2") (pinfunction "2_2") (pintype "passive"))
      (node (ref "R46") (pin "2") (pinfunction "2_2") (pintype "passive"))
      (node (ref "R55") (pin "2") (pinfunction "2_2") (pintype "passive"))
      (node (ref "R8") (pin "2") (pinfunction "2_2") (pintype "passive"))
      (node (ref "U10") (pin "9") (pinfunction "VCC_9") (pintype "power_in"))
      (node (ref "U12") (pin "1") (pinfunction "VCC_1") (pintype "bidirectional"))
      (node (ref "U13") (pin "D") (pinfunction "D_D") (pintype "passive"))
      (node (ref "U16") (pin "2") (pinfunction "S_2") (pintype "passive"))
      (node (ref "U17") (pin "2") (pinfunction "S_2") (pintype "passive"))
      (node (ref "U2") (pin "4") (pinfunction "VOUT_4") (pintype "bidirectional"))
      (node (ref "U22") (pin "2") (pinfunction "VCCA_2") (pintype "bidirectional"))
      (node (ref "U24") (pin "2") (pinfunction "VCCA_2") (pintype "bidirectional"))
      (node (ref "U26") (pin "1") (pinfunction "V+_1") (pintype "bidirectional"))
    )
    (net (code "6") (name "+10V") (class "Default")
      (node (ref "C35") (pin "1") (pinfunction "1_1") (pintype "bidirectional"))
      (node (ref "D1") (pin "C") (pinfunction "C_C") (pintype "bidirectional"))
      (node (ref "J6") (pin "36") (pinfunction "36_36") (pintype "bidirectional"))
      (node (ref "U26") (pin "5") (pinfunction "OUT_5") (pintype "bidirectional"))
    )
    (net (code "7") (name "/ADC") (class "Default")
      (node (ref "R5") (pin "1") (pinfunction "1_1") (pintype "passive"))
      (node (ref "R7") (pin "2") (pinfunction "2_2") (pintype "passive"))
      (node (ref "U10") (pin "5") (pinfunction "PA0_5") (pintype "bidirectional"))
    )
    (net (code "8") (name "/AIN1") (class "Default")
      (node (ref "R4") (pin "1") (pinfunction "1_1") (pintype "passive"))
      (node (ref "R6") (pin "1") (pinfunction "1_1") (pintype "passive"))
      (node (ref "U10") (pin "3") (pinfunction "PA2_3") (pintype "bidirectional"))
    )
    (net (code "9") (name "/B0") (class "Default")
      (node (ref "J6") (pin "2") (pinfunction "2_2") (pintype "bidirectional"))
      (node (ref "U11") (pin "11") (pinfunction "D8_11") (pintype "bidirectional"))
    )
    (net (code "10") (name "/B1") (class "Default")
      (node (ref "J6") (pin "3") (pinfunction "3_3") (pintype "bidirectional"))
      (node (ref "U11") (pin "12") (pinfunction "D7_12") (pintype "bidirectional"))
    )
    (net (code "11") (name "/B2") (class "Default")
      (node (ref "J6") (pin "4") (pinfunction "4_4") (pintype "bidirectional"))
      (node (ref "U11") (pin "13") (pinfunction "D6_13") (pintype "bidirectional"))
    )
    (net (code "12") (name "/B3") (class "Default")
      (node (ref "J6") (pin "5") (pinfunction "5_5") (pintype "bidirectional"))
      (node (ref "U11") (pin "14") (pinfunction "D22_14") (pintype "bidirectional"))
    )
    (net (code "13") (name "/B4") (class "Default")
      (node (ref "J6") (pin "6") (pinfunction "6_6") (pintype "bidirectional"))
      (node (ref "U11") (pin "15") (pinfunction "D21_15") (pintype "bidirectional"))
    )
    (net (code "14") (name "/B5") (class "Default")
      (node (ref "J6") (pin "7") (pinfunction "7_7") (pintype "bidirectional"))
      (node (ref "U11") (pin "16") (pinfunction "D5_16") (pintype "bidirectional"))
    )
    (net (code "15") (name "/B6") (class "Default")
      (node (ref "J6") (pin "10") (pinfunction "10_10") (pintype "bidirectional"))
      (node (ref "U11") (pin "18") (pinfunction "D4_18") (pintype "bidirectional"))
    )
    (net (code "16") (name "/B7") (class "Default")
      (node (ref "J6") (pin "11") (pinfunction "11_11") (pintype "bidirectional"))
      (node (ref "U11") (pin "19") (pinfunction "D3_19") (pintype "bidirectional"))
    )
    (net (code "17") (name "/BACKLIGHT_PWM") (class "Default")
      (node (ref "R54") (pin "2") (pinfunction "2_2") (pintype "passive"))
      (node (ref "U$1") (pin "J2.6") (pinfunction "PM_MPP4_J2.6") (pintype "bidirectional"))
      (node (ref "U27") (pin "G") (pinfunction "G_G") (pintype "passive"))
    )
    (net (code "18") (name "/BATT_CNTL") (class "Default")
      (node (ref "R3") (pin "2") (pinfunction "2_2") (pintype "passive"))
      (node (ref "U10") (pin "17") (pinfunction "PA5_17") (pintype "bidirectional"))
      (node (ref "U6") (pin "1") (pinfunction "G_1") (pintype "passive"))
    )
    (net (code "19") (name "/BOOT_CONFIG_0") (class "Default")
      (node (ref "U$1") (pin "J2.24") (pinfunction "GPIO80_J2.24") (pintype "bidirectional"))
    )
    (net (code "20") (name "/BOOT_CONFIG_1") (class "Default")
      (node (ref "S1") (pin "6") (pinfunction "6_6") (pintype "bidirectional"))
      (node (ref "U$1") (pin "J2.22") (pinfunction "GPIO81_J2.22") (pintype "bidirectional"))
    )
    (net (code "21") (name "/BOOT_CONFIG_2") (class "Default")
      (node (ref "U$1") (pin "J2.33") (pinfunction "GPIO82_J2.33") (pintype "bidirectional"))
    )
    (net (code "22") (name "/BOOT_CONFIG_3") (class "Default")
      (node (ref "U$1") (pin "J2.26") (pinfunction "GPIO83_J2.26") (pintype "bidirectional"))
    )
    (net (code "23") (name "/BOOT_CONFIG_5") (class "Default")
      (node (ref "R10") (pin "1") (pinfunction "1_1") (pintype "passive"))
      (node (ref "U$1") (pin "J2.35") (pinfunction "GPIO86_J2.35") (pintype "bidirectional"))
    )
    (net (code "24") (name "/CABC") (class "Default")
      (node (ref "J6") (pin "8") (pinfunction "8_8") (pintype "bidirectional"))
    )
    (net (code "25") (name "/CAM1_PWDN") (class "Default")
      (node (ref "J2") (pin "12") (pinfunction "12_12") (pintype "bidirectional"))
      (node (ref "U$1") (pin "J2.84") (pinfunction "GPIO33_J2.84") (pintype "bidirectional"))
    )
    (net (code "26") (name "/CAM1_RST") (class "Default")
      (node (ref "J2") (pin "8") (pinfunction "8_8") (pintype "bidirectional"))
      (node (ref "U$1") (pin "J1.82") (pinfunction "GPIO28_J1.82") (pintype "bidirectional"))
    )
    (net (code "27") (name "/CAM1_XCLK") (class "Default")
      (node (ref "J2") (pin "23") (pinfunction "23_23") (pintype "bidirectional"))
      (node (ref "U$1") (pin "J1.80") (pinfunction "GPIO27_J1.80") (pintype "bidirectional"))
    )
    (net (code "28") (name "/CHARGER_VCC") (class "Default")
      (node (ref "C23") (pin "1") (pinfunction "1_1") (pintype "bidirectional"))
      (node (ref "R17") (pin "2") (pinfunction "2_2") (pintype "passive"))
      (node (ref "U$1") (pin "J1.21") (pinfunction "USB_VBUS_J1.21") (pintype "bidirectional"))
      (node (ref "U14") (pin "3") (pinfunction "D_3") (pintype "passive"))
      (node (ref "U21") (pin "1") (pinfunction "VDD_1") (pintype "bidirectional"))
      (node (ref "U21") (pin "2") (pinfunction "VDD_2") (pintype "bidirectional"))
    )
    (net (code "29") (name "/CHARGE_STAT1") (class "Default")
      (node (ref "R27") (pin "1") (pinfunction "1_1") (pintype "passive"))
      (node (ref "U$1") (pin "J2.48") (pinfunction "GPIO50_J2.48") (pintype "bidirectional"))
      (node (ref "U21") (pin "3") (pinfunction "STAT1_3") (pintype "bidirectional"))
    )
    (net (code "30") (name "/CHARGE_STAT2") (class "Default")
      (node (ref "R28") (pin "1") (pinfunction "1_1") (pintype "passive"))
      (node (ref "U$1") (pin "J2.50") (pinfunction "GPIO51_J2.50") (pintype "bidirectional"))
      (node (ref "U21") (pin "4") (pinfunction "STAT2_4") (pintype "bidirectional"))
    )
    (net (code "31") (name "/CLKX") (class "Default")
      (node (ref "J6") (pin "17") (pinfunction "17_17") (pintype "bidirectional"))
      (node (ref "U11") (pin "41") (pinfunction "CLKOUT_41") (pintype "bidirectional"))
    )
    (net (code "32") (name "/COM") (class "Default")
      (node (ref "C32") (pin "1") (pinfunction "1_1") (pintype "bidirectional"))
      (node (ref "J6") (pin "38") (pinfunction "38_38") (pintype "bidirectional"))
    )
    (net (code "33") (name "/CSTN") (class "Default")
      (node (ref "C33") (pin "1") (pinfunction "1_1") (pintype "bidirectional"))
      (node (ref "J6") (pin "37") (pinfunction "37_37") (pintype "bidirectional"))
    )
    (net (code "34") (name "/DE") (class "Default")
      (node (ref "J6") (pin "16") (pinfunction "16_16") (pintype "bidirectional"))
      (node (ref "U11") (pin "22") (pinfunction "D0_22") (pintype "bidirectional"))
    )
    (net (code "35") (name "/DSI_EN") (class "Default")
      (node (ref "C21") (pin "1") (pinfunction "1_1") (pintype "bidirectional"))
      (node (ref "R14") (pin "2") (pinfunction "2_2") (pintype "passive"))
      (node (ref "R57") (pin "1") (pinfunction "1_1") (pintype "passive"))
      (node (ref "R58") (pin "1") (pinfunction "1_1") (pintype "passive"))
      (node (ref "U$1") (pin "J1.76") (pinfunction "GPIO8_J1.76") (pintype "bidirectional"))
    )
    (net (code "36") (name "/EXT_PROG_EN") (class "Default")
      (node (ref "U$1") (pin "J2.14") (pinfunction "GPIO120_J2.14") (pintype "bidirectional"))
      (node (ref "U23") (pin "G") (pinfunction "G_G") (pintype "passive"))
    )
    (net (code "37") (name "/FORCED_USB_BOOT") (class "Default")
      (node (ref "S1") (pin "2") (pinfunction "2_2") (pintype "bidirectional"))
      (node (ref "U$1") (pin "J1.87") (pinfunction "GPIO37_J1.87") (pintype "bidirectional"))
    )
    (net (code "38") (name "/FUSED_VBATT") (class "Default")
      (node (ref "C2") (pin "1") (pinfunction "1_1") (pintype "bidirectional"))
      (node (ref "F1") (pin "2") (pinfunction "2_2") (pintype "passive"))
      (node (ref "L1") (pin "P$2") (pinfunction "2_P$2") (pintype "passive"))
      (node (ref "R3") (pin "1") (pinfunction "1_1") (pintype "passive"))
      (node (ref "R4") (pin "2") (pinfunction "2_2") (pintype "passive"))
      (node (ref "R7") (pin "1") (pinfunction "1_1") (pintype "passive"))
      (node (ref "U3") (pin "1") (pinfunction "VIN_1") (pintype "bidirectional"))
      (node (ref "U3") (pin "3") (pinfunction "EN_3") (pintype "bidirectional"))
      (node (ref "U6") (pin "2") (pinfunction "S_2") (pintype "passive"))
    )
    (net (code "39") (name "/G0") (class "Default")
      (node (ref "J6") (pin "12") (pinfunction "12_12") (pintype "bidirectional"))
      (node (ref "U11") (pin "2") (pinfunction "D14_2") (pintype "bidirectional"))
    )
    (net (code "40") (name "/G1") (class "Default")
      (node (ref "J6") (pin "13") (pinfunction "13_13") (pintype "bidirectional"))
      (node (ref "U11") (pin "3") (pinfunction "D13_3") (pintype "bidirectional"))
    )
    (net (code "41") (name "/G2") (class "Default")
      (node (ref "J6") (pin "14") (pinfunction "14_14") (pintype "bidirectional"))
      (node (ref "U11") (pin "4") (pinfunction "D12_4") (pintype "bidirectional"))
    )
    (net (code "42") (name "/G3") (class "Default")
      (node (ref "J6") (pin "15") (pinfunction "15_15") (pintype "bidirectional"))
      (node (ref "U11") (pin "5") (pinfunction "D24_5") (pintype "bidirectional"))
    )
    (net (code "43") (name "/G4") (class "Default")
      (node (ref "J6") (pin "19") (pinfunction "19_19") (pintype "bidirectional"))
      (node (ref "U11") (pin "7") (pinfunction "D23_7") (pintype "bidirectional"))
    )
    (net (code "44") (name "/G5") (class "Default")
      (node (ref "J6") (pin "20") (pinfunction "20_20") (pintype "bidirectional"))
      (node (ref "U11") (pin "8") (pinfunction "D11_8") (pintype "bidirectional"))
    )
    (net (code "45") (name "/G6") (class "Default")
      (node (ref "J6") (pin "21") (pinfunction "21_21") (pintype "bidirectional"))
      (node (ref "U11") (pin "9") (pinfunction "D10_9") (pintype "bidirectional"))
    )
    (net (code "46") (name "/G7") (class "Default")
      (node (ref "J6") (pin "22") (pinfunction "22_22") (pintype "bidirectional"))
      (node (ref "U11") (pin "10") (pinfunction "D9_10") (pintype "bidirectional"))
    )
    (net (code "47") (name "/I2C0_SCL") (class "Default")
      (node (ref "J6") (pin "32") (pinfunction "32_32") (pintype "bidirectional"))
      (node (ref "R22") (pin "1") (pinfunction "1_1") (pintype "passive"))
      (node (ref "U$1") (pin "J1.79") (pinfunction "GPIO7_J1.79") (pintype "bidirectional"))
      (node (ref "U1") (pin "23") (pinfunction "SCL/SCLK_23") (pintype "bidirectional"))
      (node (ref "U22") (pin "12") (pinfunction "B0_12") (pintype "bidirectional"))
      (node (ref "U25") (pin "11") (pinfunction "B1_11") (pintype "bidirectional"))
      (node (ref "U8") (pin "8") (pinfunction "SCL_8") (pintype "bidirectional"))
    )
    (net (code "48") (name "/I2C0_SCL_3V3") (class "Default")
      (node (ref "J4") (pin "2") (pinfunction "2_2") (pintype "bidirectional"))
      (node (ref "U25") (pin "4") (pinfunction "A1_4") (pintype "bidirectional"))
    )
    (net (code "49") (name "/I2C0_SCL_5V") (class "Default")
      (node (ref "R40") (pin "1") (pinfunction "1_1") (pintype "passive"))
      (node (ref "U10") (pin "15") (pinfunction "PA7_15") (pintype "bidirectional"))
      (node (ref "U22") (pin "3") (pinfunction "A0_3") (pintype "bidirectional"))
    )
    (net (code "50") (name "/I2C0_SDA") (class "Default")
      (node (ref "J6") (pin "33") (pinfunction "33_33") (pintype "bidirectional"))
      (node (ref "R21") (pin "1") (pinfunction "1_1") (pintype "passive"))
      (node (ref "U$1") (pin "J1.77") (pinfunction "GPIO6_J1.77") (pintype "bidirectional"))
      (node (ref "U1") (pin "24") (pinfunction "SDA/SDI_24") (pintype "bidirectional"))
      (node (ref "U22") (pin "10") (pinfunction "B2_10") (pintype "bidirectional"))
      (node (ref "U25") (pin "12") (pinfunction "B0_12") (pintype "bidirectional"))
      (node (ref "U8") (pin "7") (pinfunction "SDA_7") (pintype "bidirectional"))
    )
    (net (code "51") (name "/I2C0_SDA_3V3") (class "Default")
      (node (ref "J4") (pin "8") (pinfunction "8_8") (pintype "bidirectional"))
      (node (ref "U25") (pin "3") (pinfunction "A0_3") (pintype "bidirectional"))
    )
    (net (code "52") (name "/I2C0_SDA_5V{slash}TPIDATA") (class "Default")
      (node (ref "R38") (pin "1") (pinfunction "1_1") (pintype "passive"))
      (node (ref "TP2") (pin "TP") (pinfunction "TP_TP") (pintype "input"))
      (node (ref "U10") (pin "12") (pinfunction "PB1_12") (pintype "bidirectional"))
      (node (ref "U22") (pin "5") (pinfunction "A2_5") (pintype "bidirectional"))
    )
    (net (code "53") (name "/I2C2_SCL") (class "Default")
      (node (ref "J2") (pin "14") (pinfunction "14_14") (pintype "bidirectional"))
      (node (ref "R30") (pin "1") (pinfunction "1_1") (pintype "passive"))
      (node (ref "U$1") (pin "J1.88") (pinfunction "GPIO30_J1.88") (pintype "bidirectional"))
    )
    (net (code "54") (name "/I2C2_SDA") (class "Default")
      (node (ref "J2") (pin "16") (pinfunction "16_16") (pintype "bidirectional"))
      (node (ref "R31") (pin "1") (pinfunction "1_1") (pintype "passive"))
      (node (ref "U$1") (pin "J1.90") (pinfunction "GPIO29_J1.90") (pintype "bidirectional"))
    )
    (net (code "55") (name "/I2C3_SCL") (class "Default")
      (node (ref "R33") (pin "1") (pinfunction "1_1") (pintype "passive"))
      (node (ref "U$1") (pin "J2.67") (pinfunction "GPIO15_J2.67") (pintype "bidirectional"))
      (node (ref "U7") (pin "15") (pinfunction "SCL_15") (pintype "bidirectional"))
    )
    (net (code "56") (name "/I2C3_SDA") (class "Default")
      (node (ref "R32") (pin "1") (pinfunction "1_1") (pintype "passive"))
      (node (ref "U$1") (pin "J2.69") (pinfunction "GPIO14_J2.69") (pintype "bidirectional"))
      (node (ref "U7") (pin "16") (pinfunction "SDA_16") (pintype "bidirectional"))
    )
    (net (code "57") (name "/MIPI_CSI1_CLK_N") (class "Default")
      (node (ref "J2") (pin "13") (pinfunction "13_13") (pintype "bidirectional"))
      (node (ref "U$1") (pin "J1.34") (pinfunction "MIPI_CSI1_CLK_N_J1.34") (pintype "bidirectional"))
    )
    (net (code "58") (name "/MIPI_CSI1_CLK_P") (class "Default")
      (node (ref "J2") (pin "15") (pinfunction "15_15") (pintype "bidirectional"))
      (node (ref "U$1") (pin "J1.36") (pinfunction "MIPI_CSI1_CLK_P_J1.36") (pintype "bidirectional"))
    )
    (net (code "59") (name "/MIPI_CSI1_DATA0_N") (class "Default")
      (node (ref "J2") (pin "9") (pinfunction "9_9") (pintype "bidirectional"))
      (node (ref "U$1") (pin "J1.42") (pinfunction "MIPI_CSI1_DATA0_N_J1.42") (pintype "bidirectional"))
    )
    (net (code "60") (name "/MIPI_CSI1_DATA0_P") (class "Default")
      (node (ref "J2") (pin "11") (pinfunction "11_11") (pintype "bidirectional"))
      (node (ref "U$1") (pin "J1.44") (pinfunction "MIPI_CSI1_DATA0_P_J1.44") (pintype "bidirectional"))
    )
    (net (code "61") (name "/MIPI_CSI1_DATA1_N") (class "Default")
      (node (ref "J2") (pin "17") (pinfunction "17_17") (pintype "bidirectional"))
      (node (ref "U$1") (pin "J1.38") (pinfunction "MIPI_CSI1_DATA1_N_J1.38") (pintype "bidirectional"))
    )
    (net (code "62") (name "/MIPI_CSI1_DATA1_P") (class "Default")
      (node (ref "J2") (pin "19") (pinfunction "19_19") (pintype "bidirectional"))
      (node (ref "U$1") (pin "J1.40") (pinfunction "MIPI_CSI1_DATA1_P_J1.40") (pintype "bidirectional"))
    )
    (net (code "63") (name "/MIPI_DSI0_CLK_N") (class "Default")
      (node (ref "U$1") (pin "J1.24") (pinfunction "MIPI_DSI0_CLK_N_J1.24") (pintype "bidirectional"))
      (node (ref "U7") (pin "25") (pinfunction "DACN_25") (pintype "bidirectional"))
    )
    (net (code "64") (name "/MIPI_DSI0_CLK_P") (class "Default")
      (node (ref "U$1") (pin "J1.26") (pinfunction "MIPI_DSI0_CLK_P_J1.26") (pintype "bidirectional"))
      (node (ref "U7") (pin "24") (pinfunction "DACP_24") (pintype "bidirectional"))
    )
    (net (code "65") (name "/MIPI_DSI0_DATA0_N") (class "Default")
      (node (ref "U$1") (pin "J1.28") (pinfunction "MIPI_DSI0_DATA0_N_J1.28") (pintype "bidirectional"))
      (node (ref "U7") (pin "20") (pinfunction "DA0N_20") (pintype "bidirectional"))
    )
    (net (code "66") (name "/MIPI_DSI0_DATA0_P") (class "Default")
      (node (ref "U$1") (pin "J1.30") (pinfunction "MIPI_DSI0_DATA0_P_J1.30") (pintype "bidirectional"))
      (node (ref "U7") (pin "19") (pinfunction "DA0P_19") (pintype "bidirectional"))
    )
    (net (code "67") (name "/MIPI_DSI0_DATA1_N") (class "Default")
      (node (ref "U$1") (pin "J1.20") (pinfunction "MIPI_DSI0_DATA1_N_J1.20") (pintype "bidirectional"))
      (node (ref "U7") (pin "22") (pinfunction "DA1N_22") (pintype "bidirectional"))
    )
    (net (code "68") (name "/MIPI_DSI0_DATA1_P") (class "Default")
      (node (ref "U$1") (pin "J1.22") (pinfunction "MIPI_DSI0_DATA1_P_J1.22") (pintype "bidirectional"))
      (node (ref "U7") (pin "21") (pinfunction "DA1P_21") (pintype "bidirectional"))
    )
    (net (code "69") (name "/MIPI_DSI0_DATA2_N") (class "Default")
      (node (ref "U$1") (pin "J1.16") (pinfunction "MIPI_DSI0_DATA2_N_J1.16") (pintype "bidirectional"))
      (node (ref "U7") (pin "28") (pinfunction "DA2N_28") (pintype "bidirectional"))
    )
    (net (code "70") (name "/MIPI_DSI0_DATA2_P") (class "Default")
      (node (ref "U$1") (pin "J1.18") (pinfunction "MIPI_DSI0_DATA2_P_J1.18") (pintype "bidirectional"))
      (node (ref "U7") (pin "27") (pinfunction "DA2P_27") (pintype "bidirectional"))
    )
    (net (code "71") (name "/MIPI_DSI0_DATA3_N") (class "Default")
      (node (ref "U$1") (pin "J1.12") (pinfunction "MIPI_DSI0_DATA3_N_J1.12") (pintype "bidirectional"))
      (node (ref "U7") (pin "30") (pinfunction "DA3N_30") (pintype "bidirectional"))
    )
    (net (code "72") (name "/MIPI_DSI0_DATA3_P") (class "Default")
      (node (ref "U$1") (pin "J1.14") (pinfunction "MIPI_DSI0_DATA3_P_J1.14") (pintype "bidirectional"))
      (node (ref "U7") (pin "29") (pinfunction "DA3P_29") (pintype "bidirectional"))
    )
    (net (code "73") (name "/PHONE_ON_N") (class "Default")
      (node (ref "R9") (pin "1") (pinfunction "1_1") (pintype "passive"))
      (node (ref "U$1") (pin "J2.9") (pinfunction "PHONE_ON_N_J2.9") (pintype "bidirectional"))
      (node (ref "U9") (pin "D") (pinfunction "D_D") (pintype "passive"))
    )
    (net (code "74") (name "/PM_RESIN_N") (class "Default")
      (node (ref "R24") (pin "1") (pinfunction "1_1") (pintype "passive"))
      (node (ref "S1") (pin "8") (pinfunction "8_8") (pintype "bidirectional"))
      (node (ref "U$1") (pin "J2.7") (pinfunction "PM_RESIN_N_J2.7") (pintype "bidirectional"))
    )
    (net (code "75") (name "/R0") (class "Default")
      (node (ref "J6") (pin "23") (pinfunction "23_23") (pintype "bidirectional"))
      (node (ref "U11") (pin "38") (pinfunction "D20_38") (pintype "bidirectional"))
    )
    (net (code "76") (name "/R1") (class "Default")
      (node (ref "J6") (pin "24") (pinfunction "24_24") (pintype "bidirectional"))
      (node (ref "U11") (pin "39") (pinfunction "D19_39") (pintype "bidirectional"))
    )
    (net (code "77") (name "/R2") (class "Default")
      (node (ref "J6") (pin "26") (pinfunction "26_26") (pintype "bidirectional"))
      (node (ref "U11") (pin "40") (pinfunction "D18_40") (pintype "bidirectional"))
    )
    (net (code "78") (name "/R3") (class "Default")
      (node (ref "J6") (pin "27") (pinfunction "27_27") (pintype "bidirectional"))
      (node (ref "U11") (pin "42") (pinfunction "D26_42") (pintype "bidirectional"))
    )
    (net (code "79") (name "/R4") (class "Default")
      (node (ref "J6") (pin "28") (pinfunction "28_28") (pintype "bidirectional"))
      (node (ref "U11") (pin "46") (pinfunction "D25_46") (pintype "bidirectional"))
    )
    (net (code "80") (name "/R5") (class "Default")
      (node (ref "J6") (pin "29") (pinfunction "29_29") (pintype "bidirectional"))
      (node (ref "U11") (pin "47") (pinfunction "D17_47") (pintype "bidirectional"))
    )
    (net (code "81") (name "/R6") (class "Default")
      (node (ref "J6") (pin "30") (pinfunction "30_30") (pintype "bidirectional"))
      (node (ref "U11") (pin "48") (pinfunction "D16_48") (pintype "bidirectional"))
    )
    (net (code "82") (name "/R7") (class "Default")
      (node (ref "J6") (pin "31") (pinfunction "31_31") (pintype "bidirectional"))
      (node (ref "U11") (pin "1") (pinfunction "D15_1") (pintype "bidirectional"))
    )
    (net (code "83") (name "/RESETB") (class "Default")
      (node (ref "J6") (pin "34") (pinfunction "34_34") (pintype "bidirectional"))
      (node (ref "R50") (pin "1") (pinfunction "1_1") (pintype "passive"))
    )
    (net (code "84") (name "/RX1") (class "Default")
      (node (ref "J5") (pin "2") (pinfunction "2_2") (pintype "bidirectional"))
      (node (ref "R34") (pin "2") (pinfunction "2_2") (pintype "passive"))
    )
    (net (code "85") (name "/RX2") (class "Default")
      (node (ref "J5") (pin "1") (pinfunction "1_1") (pintype "bidirectional"))
      (node (ref "R35") (pin "2") (pinfunction "2_2") (pintype "passive"))
    )
    (net (code "86") (name "/RX3") (class "Default")
      (node (ref "J5") (pin "3") (pinfunction "3_3") (pintype "bidirectional"))
      (node (ref "R36") (pin "2") (pinfunction "2_2") (pintype "passive"))
    )
    (net (code "87") (name "/SDC2_CLK") (class "Default")
      (node (ref "U$1") (pin "J1.59") (pinfunction "SDC2_CLK_J1.59") (pintype "bidirectional"))
      (node (ref "U20") (pin "5") (pinfunction "CLK_5") (pintype "bidirectional"))
    )
    (net (code "88") (name "/SDC2_CMD") (class "Default")
      (node (ref "U$1") (pin "J1.57") (pinfunction "SDC2_CMD_J1.57") (pintype "bidirectional"))
      (node (ref "U20") (pin "3") (pinfunction "CMD_3") (pintype "bidirectional"))
    )
    (net (code "89") (name "/SDC2_DATA_0") (class "Default")
      (node (ref "U$1") (pin "J1.53") (pinfunction "SDC2_DATA_0_J1.53") (pintype "bidirectional"))
      (node (ref "U20") (pin "7") (pinfunction "DAT0_7") (pintype "bidirectional"))
    )
    (net (code "90") (name "/SDC2_DATA_1") (class "Default")
      (node (ref "U$1") (pin "J1.55") (pinfunction "SDC2_DATA_1_J1.55") (pintype "bidirectional"))
      (node (ref "U20") (pin "8") (pinfunction "DAT1_8") (pintype "bidirectional"))
    )
    (net (code "91") (name "/SDC2_DATA_2") (class "Default")
      (node (ref "U$1") (pin "J1.51") (pinfunction "SDC2_DATA_2_J1.51") (pintype "bidirectional"))
      (node (ref "U20") (pin "1") (pinfunction "DAT2_1") (pintype "bidirectional"))
    )
    (net (code "92") (name "/SDC2_DATA_3") (class "Default")
      (node (ref "U$1") (pin "J1.49") (pinfunction "SDC2_DATA_3_J1.49") (pintype "bidirectional"))
      (node (ref "U20") (pin "2") (pinfunction "CD/DAT3_2") (pintype "bidirectional"))
    )
    (net (code "93") (name "/SPI0_CLK") (class "Default")
      (node (ref "J1") (pin "16") (pinfunction "16_16") (pintype "bidirectional"))
      (node (ref "U$1") (pin "J1.63") (pinfunction "GPIO19_J1.63") (pintype "bidirectional"))
    )
    (net (code "94") (name "/SPI0_CS") (class "Default")
      (node (ref "J1") (pin "12") (pinfunction "12_12") (pintype "bidirectional"))
      (node (ref "U$1") (pin "J1.67") (pinfunction "GPIO18_J1.67") (pintype "bidirectional"))
    )
    (net (code "95") (name "/SPI0_MISO") (class "Default")
      (node (ref "J1") (pin "11") (pinfunction "11_11") (pintype "bidirectional"))
      (node (ref "U$1") (pin "J1.69") (pinfunction "GPIO17_J1.69") (pintype "bidirectional"))
    )
    (net (code "96") (name "/SPI0_MOSI") (class "Default")
      (node (ref "J1") (pin "15") (pinfunction "15_15") (pintype "bidirectional"))
      (node (ref "U$1") (pin "J1.65") (pinfunction "GPIO16_J1.65") (pintype "bidirectional"))
    )
    (net (code "97") (name "/TEST_HV") (class "Default")
      (node (ref "J6") (pin "39") (pinfunction "39_39") (pintype "bidirectional"))
    )
    (net (code "98") (name "/TPICLK") (class "Default")
      (node (ref "TP1") (pin "TP") (pinfunction "TP_TP") (pintype "input"))
      (node (ref "U10") (pin "11") (pinfunction "PB0_11") (pintype "bidirectional"))
      (node (ref "U24") (pin "3") (pinfunction "A0_3") (pintype "bidirectional"))
    )
    (net (code "99") (name "/TPICLK_1V8") (class "Default")
      (node (ref "U$1") (pin "J2.87") (pinfunction "GPIO32_J2.87") (pintype "bidirectional"))
      (node (ref "U24") (pin "12") (pinfunction "B0_12") (pintype "bidirectional"))
    )
    (net (code "100") (name "/UART1_RX") (class "Default")
      (node (ref "JP1") (pin "2") (pinfunction "2_2") (pintype "passive"))
      (node (ref "U$1") (pin "J1.85") (pinfunction "GPIO5_J1.85") (pintype "bidirectional"))
    )
    (net (code "101") (name "/UART1_TX") (class "Default")
      (node (ref "JP1") (pin "1") (pinfunction "1_1") (pintype "passive"))
      (node (ref "U$1") (pin "J1.83") (pinfunction "GPIO4_J1.83") (pintype "bidirectional"))
    )
    (net (code "102") (name "/USB_HS_D_N") (class "Default")
      (node (ref "J7") (pin "A7") (pinfunction "D-_A7") (pintype "bidirectional"))
      (node (ref "J7") (pin "B7") (pinfunction "D-_B7") (pintype "bidirectional"))
      (node (ref "U$1") (pin "J2.32") (pinfunction "USB_HS_D_N_J2.32") (pintype "bidirectional"))
    )
    (net (code "103") (name "/USB_HS_D_P") (class "Default")
      (node (ref "J7") (pin "A6") (pinfunction "D+_A6") (pintype "bidirectional"))
      (node (ref "J7") (pin "B6") (pinfunction "D+_B6") (pintype "bidirectional"))
      (node (ref "U$1") (pin "J2.34") (pinfunction "USB_HS_D_P_J2.34") (pintype "bidirectional"))
    )
    (net (code "104") (name "/USB_HS_ID") (class "Default")
      (node (ref "R23") (pin "2") (pinfunction "2_2") (pintype "passive"))
      (node (ref "S1") (pin "4") (pinfunction "4_4") (pintype "bidirectional"))
      (node (ref "U$1") (pin "J2.64") (pinfunction "GPIO121_J2.64") (pintype "bidirectional"))
      (node (ref "U13") (pin "G") (pinfunction "G_G") (pintype "passive"))
      (node (ref "U15") (pin "G") (pinfunction "G_G") (pintype "passive"))
    )
    (net (code "105") (name "/USB_POW") (class "Default")
      (node (ref "R16") (pin "1") (pinfunction "1_1") (pintype "passive"))
      (node (ref "R55") (pin "1") (pinfunction "1_1") (pintype "passive"))
      (node (ref "U14") (pin "1") (pinfunction "G_1") (pintype "passive"))
      (node (ref "U15") (pin "D") (pinfunction "D_D") (pintype "passive"))
      (node (ref "U17") (pin "1") (pinfunction "G_1") (pintype "passive"))
    )
    (net (code "106") (name "/VBATT_IN") (class "Default")
      (node (ref "C22") (pin "1") (pinfunction "1_1") (pintype "bidirectional"))
      (node (ref "J3") (pin "1") (pinfunction "1_1") (pintype "bidirectional"))
      (node (ref "U21") (pin "10") (pinfunction "VBAT_10") (pintype "bidirectional"))
      (node (ref "U21") (pin "9") (pinfunction "VBAT_9") (pintype "bidirectional"))
      (node (ref "U5") (pin "3") (pinfunction "D_3") (pintype "passive"))
    )
    (net (code "107") (name "/VREG_L11_SDC") (class "Default")
      (node (ref "C1") (pin "1") (pinfunction "1_1") (pintype "bidirectional"))
      (node (ref "U$1") (pin "J2.1") (pinfunction "VREG_L11_SDC_J2.1") (pintype "bidirectional"))
      (node (ref "U$1") (pin "J2.3") (pinfunction "VREG_L11_SDC_J2.3") (pintype "bidirectional"))
      (node (ref "U20") (pin "4") (pinfunction "VDD_4") (pintype "bidirectional"))
    )
    (net (code "108") (name "/~{FINGER_INT_1V8}") (class "Default")
      (node (ref "J1") (pin "8") (pinfunction "8_8") (pintype "bidirectional"))
      (node (ref "R48") (pin "1") (pinfunction "1_1") (pintype "passive"))
      (node (ref "U$1") (pin "J1.73") (pinfunction "GPIO23_J1.73") (pintype "bidirectional"))
      (node (ref "U24") (pin "11") (pinfunction "B1_11") (pintype "bidirectional"))
    )
    (net (code "109") (name "/~{FINGER_INT_5V}") (class "Default")
      (node (ref "R46") (pin "1") (pinfunction "1_1") (pintype "passive"))
      (node (ref "U10") (pin "14") (pinfunction "PB2_14") (pintype "bidirectional"))
      (node (ref "U24") (pin "4") (pinfunction "A1_4") (pintype "bidirectional"))
    )
    (net (code "110") (name "/~{FINGER_RST}") (class "Default")
      (node (ref "J1") (pin "10") (pinfunction "10_10") (pintype "bidirectional"))
      (node (ref "R20") (pin "1") (pinfunction "1_1") (pintype "passive"))
      (node (ref "U$1") (pin "J1.75") (pinfunction "GPIO22_J1.75") (pintype "bidirectional"))
    )
    (net (code "111") (name "/~{GESTURE_INT_3V3}") (class "Default")
      (node (ref "J4") (pin "7") (pinfunction "7_7") (pintype "bidirectional"))
      (node (ref "U25") (pin "5") (pinfunction "A2_5") (pintype "bidirectional"))
    )
    (net (code "112") (name "/~{GESTURE_INT}") (class "Default")
      (node (ref "R49") (pin "1") (pinfunction "1_1") (pintype "passive"))
      (node (ref "U$1") (pin "J2.52") (pinfunction "GPIO69_J2.52") (pintype "bidirectional"))
      (node (ref "U25") (pin "10") (pinfunction "B2_10") (pintype "bidirectional"))
    )
    (net (code "113") (name "/~{SHUTDOWN_INT_1V8}") (class "Default")
      (node (ref "R43") (pin "1") (pinfunction "1_1") (pintype "passive"))
      (node (ref "U$1") (pin "J2.88") (pinfunction "GPIO36_J2.88") (pintype "bidirectional"))
      (node (ref "U22") (pin "9") (pinfunction "B3_9") (pintype "bidirectional"))
    )
    (net (code "114") (name "/~{SHUTDOWN_INT_5V}") (class "Default")
      (node (ref "R41") (pin "1") (pinfunction "1_1") (pintype "passive"))
      (node (ref "U10") (pin "2") (pinfunction "PA3_2") (pintype "bidirectional"))
      (node (ref "U22") (pin "6") (pinfunction "A3_6") (pintype "bidirectional"))
    )
    (net (code "115") (name "/~{TOUCH_INT_1V8}") (class "Default")
      (node (ref "R39") (pin "1") (pinfunction "1_1") (pintype "passive"))
      (node (ref "U$1") (pin "J2.12") (pinfunction "GPIO21_J2.12") (pintype "bidirectional"))
      (node (ref "U24") (pin "10") (pinfunction "B2_10") (pintype "bidirectional"))
      (node (ref "U8") (pin "6") (pinfunction "RDY_6") (pintype "bidirectional"))
    )
    (net (code "116") (name "/~{TOUCH_INT_5V}") (class "Default")
      (node (ref "R45") (pin "1") (pinfunction "1_1") (pintype "passive"))
      (node (ref "U10") (pin "1") (pinfunction "PA4_1") (pintype "bidirectional"))
      (node (ref "U24") (pin "5") (pinfunction "A2_5") (pintype "bidirectional"))
    )
    (net (code "117") (name "/~{TPI_RST_1V8}") (class "Default")
      (node (ref "R42") (pin "1") (pinfunction "1_1") (pintype "passive"))
      (node (ref "U$1") (pin "J2.86") (pinfunction "GPIO34_J2.86") (pintype "bidirectional"))
      (node (ref "U22") (pin "11") (pinfunction "B1_11") (pintype "bidirectional"))
    )
    (net (code "118") (name "/~{TPI_RST_5V}") (class "Default")
      (node (ref "R2") (pin "2") (pinfunction "2_2") (pintype "passive"))
      (node (ref "TP3") (pin "TP") (pinfunction "TP_TP") (pintype "input"))
      (node (ref "U10") (pin "13") (pinfunction "PB3_13") (pintype "bidirectional"))
      (node (ref "U22") (pin "4") (pinfunction "A1_4") (pintype "bidirectional"))
    )
    (net (code "119") (name "GND") (class "Default")
      (node (ref "C1") (pin "2") (pinfunction "2_2") (pintype "bidirectional"))
      (node (ref "C10") (pin "2") (pinfunction "2_2") (pintype "bidirectional"))
      (node (ref "C11") (pin "2") (pinfunction "2_2") (pintype "bidirectional"))
      (node (ref "C12") (pin "2") (pinfunction "2_2") (pintype "bidirectional"))
      (node (ref "C13") (pin "2") (pinfunction "2_2") (pintype "bidirectional"))
      (node (ref "C14") (pin "2") (pinfunction "2_2") (pintype "bidirectional"))
      (node (ref "C15") (pin "1") (pinfunction "1_1") (pintype "bidirectional"))
      (node (ref "C16") (pin "2") (pinfunction "2_2") (pintype "bidirectional"))
      (node (ref "C17") (pin "2") (pinfunction "2_2") (pintype "bidirectional"))
      (node (ref "C18") (pin "2") (pinfunction "2_2") (pintype "bidirectional"))
      (node (ref "C19") (pin "2") (pinfunction "2_2") (pintype "bidirectional"))
      (node (ref "C2") (pin "2") (pinfunction "2_2") (pintype "bidirectional"))
      (node (ref "C20") (pin "2") (pinfunction "2_2") (pintype "bidirectional"))
      (node (ref "C21") (pin "2") (pinfunction "2_2") (pintype "bidirectional"))
      (node (ref "C22") (pin "2") (pinfunction "2_2") (pintype "bidirectional"))
      (node (ref "C23") (pin "2") (pinfunction "2_2") (pintype "bidirectional"))
      (node (ref "C24") (pin "2") (pinfunction "2_2") (pintype "bidirectional"))
      (node (ref "C25") (pin "2") (pinfunction "2_2") (pintype "bidirectional"))
      (node (ref "C26") (pin "2") (pinfunction "2_2") (pintype "bidirectional"))
      (node (ref "C27") (pin "2") (pinfunction "2_2") (pintype "bidirectional"))
      (node (ref "C28") (pin "2") (pinfunction "2_2") (pintype "bidirectional"))
      (node (ref "C29") (pin "2") (pinfunction "2_2") (pintype "bidirectional"))
      (node (ref "C3") (pin "2") (pinfunction "2_2") (pintype "bidirectional"))
      (node (ref "C31") (pin "2") (pinfunction "2_2") (pintype "bidirectional"))
      (node (ref "C32") (pin "2") (pinfunction "2_2") (pintype "bidirectional"))
      (node (ref "C33") (pin "2") (pinfunction "2_2") (pintype "bidirectional"))
      (node (ref "C35") (pin "2") (pinfunction "2_2") (pintype "bidirectional"))
      (node (ref "C4") (pin "2") (pinfunction "2_2") (pintype "bidirectional"))
      (node (ref "C5") (pin "2") (pinfunction "2_2") (pintype "bidirectional"))
      (node (ref "C50") (pin "2") (pinfunction "2_2") (pintype "bidirectional"))
      (node (ref "C6") (pin "2") (pinfunction "2_2") (pintype "bidirectional"))
      (node (ref "C7") (pin "1") (pinfunction "1_1") (pintype "bidirectional"))
      (node (ref "C8") (pin "2") (pinfunction "2_2") (pintype "bidirectional"))
      (node (ref "C9") (pin "2") (pinfunction "2_2") (pintype "bidirectional"))
      (node (ref "J1") (pin "13") (pinfunction "13_13") (pintype "bidirectional"))
      (node (ref "J1") (pin "14") (pinfunction "14_14") (pintype "bidirectional"))
      (node (ref "J1") (pin "3") (pinfunction "3_3") (pintype "bidirectional"))
      (node (ref "J1") (pin "4") (pinfunction "4_4") (pintype "bidirectional"))
      (node (ref "J1") (pin "9") (pinfunction "9_9") (pintype "bidirectional"))
      (node (ref "J2") (pin "18") (pinfunction "18_18") (pintype "bidirectional"))
      (node (ref "J2") (pin "21") (pinfunction "21_21") (pintype "bidirectional"))
      (node (ref "J2") (pin "25") (pinfunction "25_25") (pintype "bidirectional"))
      (node (ref "J2") (pin "26") (pinfunction "26_26") (pintype "bidirectional"))
      (node (ref "J2") (pin "27") (pinfunction "27_27") (pintype "bidirectional"))
      (node (ref "J2") (pin "29") (pinfunction "29_29") (pintype "bidirectional"))
      (node (ref "J2") (pin "4") (pinfunction "4_4") (pintype "bidirectional"))
      (node (ref "J3") (pin "2") (pinfunction "2_2") (pintype "bidirectional"))
      (node (ref "J4") (pin "6") (pinfunction "6_6") (pintype "bidirectional"))
      (node (ref "J5") (pin "4") (pinfunction "4_4") (pintype "bidirectional"))
      (node (ref "J6") (pin "18") (pinfunction "18_18") (pintype "bidirectional"))
      (node (ref "J6") (pin "35") (pinfunction "35_35") (pintype "bidirectional"))
      (node (ref "J7") (pin "A1") (pinfunction "GND_A1") (pintype "power_in"))
      (node (ref "J7") (pin "A12") (pinfunction "GND_A12") (pintype "power_in"))
      (node (ref "J7") (pin "B1") (pinfunction "GND_B1") (pintype "power_in"))
      (node (ref "J7") (pin "B12") (pinfunction "GND_B12") (pintype "power_in"))
      (node (ref "J7") (pin "P$1") (pinfunction "SHIELD_P$1") (pintype "power_in"))
      (node (ref "J7") (pin "P$2") (pinfunction "SHIELD_P$2") (pintype "power_in"))
      (node (ref "J7") (pin "P$3") (pinfunction "SHIELD_P$3") (pintype "power_in"))
      (node (ref "J7") (pin "P$4") (pinfunction "SHIELD_P$4") (pintype "power_in"))
      (node (ref "J7") (pin "P$5") (pinfunction "SHIELD_P$5") (pintype "power_in"))
      (node (ref "J7") (pin "P$6") (pinfunction "SHIELD_P$6") (pintype "power_in"))
      (node (ref "JP1") (pin "3") (pinfunction "3_3") (pintype "passive"))
      (node (ref "R12") (pin "1") (pinfunction "1_1") (pintype "passive"))
      (node (ref "R13") (pin "1") (pinfunction "1_1") (pintype "passive"))
      (node (ref "R15") (pin "1") (pinfunction "1_1") (pintype "passive"))
      (node (ref "R17") (pin "1") (pinfunction "1_1") (pintype "passive"))
      (node (ref "R18") (pin "1") (pinfunction "1_1") (pintype "passive"))
      (node (ref "R19") (pin "2") (pinfunction "2_2") (pintype "passive"))
      (node (ref "R23") (pin "1") (pinfunction "1_1") (pintype "passive"))
      (node (ref "R25") (pin "1") (pinfunction "1_1") (pintype "passive"))
      (node (ref "R26") (pin "1") (pinfunction "1_1") (pintype "passive"))
      (node (ref "R29") (pin "1") (pinfunction "1_1") (pintype "passive"))
      (node (ref "R5") (pin "2") (pinfunction "2_2") (pintype "passive"))
      (node (ref "R53") (pin "1") (pinfunction "1_1") (pintype "passive"))
      (node (ref "R54") (pin "1") (pinfunction "1_1") (pintype "passive"))
      (node (ref "R6") (pin "2") (pinfunction "2_2") (pintype "passive"))
      (node (ref "S1") (pin "7") (pinfunction "7_7") (pintype "bidirectional"))
      (node (ref "U$1") (pin "J1.10") (pinfunction "DGND_J1.10") (pintype "bidirectional"))
      (node (ref "U$1") (pin "J1.31") (pinfunction "DGND_J1.31") (pintype "bidirectional"))
      (node (ref "U$1") (pin "J1.32") (pinfunction "DGND_J1.32") (pintype "bidirectional"))
      (node (ref "U$1") (pin "J1.37") (pinfunction "DGND_J1.37") (pintype "bidirectional"))
      (node (ref "U$1") (pin "J1.41") (pinfunction "GND_CFILT_J1.41") (pintype "bidirectional"))
      (node (ref "U$1") (pin "J1.45") (pinfunction "GND_CFILT_J1.45") (pintype "bidirectional"))
      (node (ref "U$1") (pin "J1.46") (pinfunction "DGND_J1.46") (pintype "bidirectional"))
      (node (ref "U$1") (pin "J1.47") (pinfunction "DGND_J1.47") (pintype "bidirectional"))
      (node (ref "U$1") (pin "J1.61") (pinfunction "DGND_J1.61") (pintype "bidirectional"))
      (node (ref "U$1") (pin "J1.68") (pinfunction "DGND_J1.68") (pintype "bidirectional"))
      (node (ref "U$1") (pin "J1.71") (pinfunction "DGND_J1.71") (pintype "bidirectional"))
      (node (ref "U$1") (pin "J1.78") (pinfunction "DGND_J1.78") (pintype "bidirectional"))
      (node (ref "U$1") (pin "J1.81") (pinfunction "DGND_J1.81") (pintype "bidirectional"))
      (node (ref "U$1") (pin "J1.86") (pinfunction "DGND_J1.86") (pintype "bidirectional"))
      (node (ref "U$1") (pin "J2.11") (pinfunction "DGND_J2.11") (pintype "bidirectional"))
      (node (ref "U$1") (pin "J2.15") (pinfunction "DGND_J2.15") (pintype "bidirectional"))
      (node (ref "U$1") (pin "J2.21") (pinfunction "DGND_J2.21") (pintype "bidirectional"))
      (node (ref "U$1") (pin "J2.30") (pinfunction "DGND_J2.30") (pintype "bidirectional"))
      (node (ref "U$1") (pin "J2.31") (pinfunction "DGND_J2.31") (pintype "bidirectional"))
      (node (ref "U$1") (pin "J2.36") (pinfunction "DGND_J2.36") (pintype "bidirectional"))
      (node (ref "U$1") (pin "J2.37") (pinfunction "DGND_J2.37") (pintype "bidirectional"))
      (node (ref "U$1") (pin "J2.42") (pinfunction "DGND_J2.42") (pintype "bidirectional"))
      (node (ref "U$1") (pin "J2.49") (pinfunction "DGND_J2.49") (pintype "bidirectional"))
      (node (ref "U$1") (pin "J2.5") (pinfunction "DGND_J2.5") (pintype "bidirectional"))
      (node (ref "U$1") (pin "J2.56") (pinfunction "DGND_J2.56") (pintype "bidirectional"))
      (node (ref "U$1") (pin "J2.65") (pinfunction "DGND_J2.65") (pintype "bidirectional"))
      (node (ref "U$1") (pin "J2.66") (pinfunction "DGND_J2.66") (pintype "bidirectional"))
      (node (ref "U$1") (pin "J2.77") (pinfunction "DGND_J2.77") (pintype "bidirectional"))
      (node (ref "U$1") (pin "J2.82") (pinfunction "DGND_J2.82") (pintype "bidirectional"))
      (node (ref "U$1") (pin "J2.89") (pinfunction "DGND_J2.89") (pintype "bidirectional"))
      (node (ref "U$1") (pin "J2.90") (pinfunction "DGND_J2.90") (pintype "bidirectional"))
      (node (ref "U1") (pin "11") (pinfunction "FSYNC_11") (pintype "bidirectional"))
      (node (ref "U1") (pin "18") (pinfunction "GND_18") (pintype "bidirectional"))
      (node (ref "U1") (pin "20") (pinfunction "GND_20") (pintype "bidirectional"))
      (node (ref "U10") (pin "21") (pinfunction "EPAD_21") (pintype "passive"))
      (node (ref "U10") (pin "8") (pinfunction "GND_8") (pintype "power_in"))
      (node (ref "U11") (pin "36") (pinfunction "MODE14_36") (pintype "bidirectional"))
      (node (ref "U11") (pin "45") (pinfunction "SWAP_45") (pintype "bidirectional"))
      (node (ref "U11") (pin "49") (pinfunction "GND_49") (pintype "bidirectional"))
      (node (ref "U12") (pin "6") (pinfunction "GND_6") (pintype "bidirectional"))
      (node (ref "U15") (pin "S") (pinfunction "S_S") (pintype "passive"))
      (node (ref "U18") (pin "2") (pinfunction "GND_2") (pintype "bidirectional"))
      (node (ref "U19") (pin "2") (pinfunction "GND_2") (pintype "bidirectional"))
      (node (ref "U2") (pin "2") (pinfunction "GND_2") (pintype "bidirectional"))
      (node (ref "U20") (pin "10") (pinfunction "VSS_10") (pintype "bidirectional"))
      (node (ref "U20") (pin "11") (pinfunction "VSS_11") (pintype "bidirectional"))
      (node (ref "U20") (pin "12") (pinfunction "VSS_12") (pintype "bidirectional"))
      (node (ref "U20") (pin "13") (pinfunction "VSS_13") (pintype "bidirectional"))
      (node (ref "U20") (pin "6") (pinfunction "VSS_6") (pintype "bidirectional"))
      (node (ref "U20") (pin "9") (pinfunction "VSS_9") (pintype "bidirectional"))
      (node (ref "U21") (pin "5") (pinfunction "VSS_5") (pintype "bidirectional"))
      (node (ref "U21") (pin "EXP") (pinfunction "VSS_EXP") (pintype "bidirectional"))
      (node (ref "U22") (pin "7") (pinfunction "GND_7") (pintype "bidirectional"))
      (node (ref "U23") (pin "S") (pinfunction "S_S") (pintype "passive"))
      (node (ref "U24") (pin "7") (pinfunction "GND_7") (pintype "bidirectional"))
      (node (ref "U25") (pin "7") (pinfunction "GND_7") (pintype "bidirectional"))
      (node (ref "U26") (pin "2") (pinfunction "GND_2") (pintype "bidirectional"))
      (node (ref "U26") (pin "4") (pinfunction "SD_4") (pintype "bidirectional"))
      (node (ref "U27") (pin "S") (pinfunction "S_S") (pintype "passive"))
      (node (ref "U3") (pin "2") (pinfunction "GND_2") (pintype "bidirectional"))
      (node (ref "U4") (pin "2") (pinfunction "GND_2") (pintype "bidirectional"))
      (node (ref "U5") (pin "1") (pinfunction "G_1") (pintype "passive"))
      (node (ref "U7") (pin "23") (pinfunction "GND_23") (pintype "bidirectional"))
      (node (ref "U7") (pin "26") (pinfunction "GND_26") (pintype "bidirectional"))
      (node (ref "U7") (pin "52") (pinfunction "GND_52") (pintype "bidirectional"))
      (node (ref "U7") (pin "65") (pinfunction "GND_65") (pintype "bidirectional"))
      (node (ref "U8") (pin "1") (pinfunction "GND_1") (pintype "bidirectional"))
      (node (ref "U8") (pin "EXP") (pinfunction "GND_EXP") (pintype "bidirectional"))
      (node (ref "U9") (pin "S") (pinfunction "S_S") (pintype "passive"))
    )
    (net (code "120") (name "Net-(C50-Pad1)") (class "Default")
      (node (ref "C50") (pin "1") (pinfunction "1_1") (pintype "bidirectional"))
      (node (ref "F2") (pin "1") (pinfunction "1_1") (pintype "passive"))
      (node (ref "J7") (pin "A4") (pinfunction "VBUS_A4") (pintype "power_in"))
      (node (ref "J7") (pin "A9") (pinfunction "VBUS_A9") (pintype "power_in"))
      (node (ref "J7") (pin "B4") (pinfunction "VBUS_B4") (pintype "power_in"))
      (node (ref "J7") (pin "B9") (pinfunction "VBUS_B9") (pintype "power_in"))
    )
    (net (code "121") (name "Net-(J7-CC1)") (class "Default")
      (node (ref "J7") (pin "A5") (pinfunction "CC1_A5") (pintype "bidirectional"))
      (node (ref "U12") (pin "3") (pinfunction "COM1_3") (pintype "bidirectional"))
    )
    (net (code "122") (name "Net-(J7-CC2)") (class "Default")
      (node (ref "J7") (pin "B5") (pinfunction "CC2_B5") (pintype "bidirectional"))
      (node (ref "U12") (pin "9") (pinfunction "COM2_9") (pintype "bidirectional"))
    )
    (net (code "123") (name "Net-(J8-Pad6)") (class "Default")
      (node (ref "J8") (pin "6") (pinfunction "6_6") (pintype "bidirectional"))
      (node (ref "J8") (pin "7") (pinfunction "7_7") (pintype "bidirectional"))
      (node (ref "J8") (pin "8") (pinfunction "8_8") (pintype "bidirectional"))
      (node (ref "R51") (pin "2") (pinfunction "2_2") (pintype "passive"))
    )
    (net (code "124") (name "Net-(L1-1)") (class "Default")
      (node (ref "L1") (pin "P$1") (pinfunction "1_P$1") (pintype "passive"))
      (node (ref "U2") (pin "1") (pinfunction "SW_1") (pintype "bidirectional"))
    )
    (net (code "125") (name "Net-(R11-Pad1)") (class "Default")
      (node (ref "R11") (pin "1") (pinfunction "1_1") (pintype "passive"))
      (node (ref "S1") (pin "1") (pinfunction "1_1") (pintype "bidirectional"))
    )
    (net (code "126") (name "Net-(R51-Pad1)") (class "Default")
      (node (ref "R51") (pin "1") (pinfunction "1_1") (pintype "passive"))
      (node (ref "U27") (pin "D") (pinfunction "D_D") (pintype "passive"))
    )
    (net (code "127") (name "Net-(R52-Pad1)") (class "Default")
      (node (ref "R52") (pin "1") (pinfunction "1_1") (pintype "passive"))
      (node (ref "S1") (pin "5") (pinfunction "5_5") (pintype "bidirectional"))
    )
    (net (code "128") (name "Net-(U1-REGOUT)") (class "Default")
      (node (ref "C20") (pin "1") (pinfunction "1_1") (pintype "bidirectional"))
      (node (ref "U1") (pin "10") (pinfunction "REGOUT_10") (pintype "bidirectional"))
    )
    (net (code "129") (name "Net-(U5-S)") (class "Default")
      (node (ref "F1") (pin "1") (pinfunction "1_1") (pintype "passive"))
      (node (ref "U5") (pin "2") (pinfunction "S_2") (pintype "passive"))
    )
    (net (code "130") (name "Net-(U7-ADDR)") (class "Default")
      (node (ref "R25") (pin "2") (pinfunction "2_2") (pintype "passive"))
      (node (ref "U7") (pin "64") (pinfunction "ADDR_64") (pintype "bidirectional"))
    )
    (net (code "131") (name "Net-(U7-EN)") (class "Default")
      (node (ref "R57") (pin "2") (pinfunction "2_2") (pintype "passive"))
      (node (ref "U7") (pin "2") (pinfunction "EN_2") (pintype "bidirectional"))
    )
    (net (code "132") (name "Net-(U7-REFCLK)") (class "Default")
      (node (ref "R53") (pin "2") (pinfunction "2_2") (pintype "passive"))
      (node (ref "U7") (pin "17") (pinfunction "REFCLK_17") (pintype "bidirectional"))
    )
    (net (code "133") (name "Net-(U7-VCORE)") (class "Default")
      (node (ref "C17") (pin "1") (pinfunction "1_1") (pintype "bidirectional"))
      (node (ref "U7") (pin "31") (pinfunction "VCORE_31") (pintype "bidirectional"))
    )
    (net (code "134") (name "Net-(U8-CRX1)") (class "Default")
      (node (ref "R34") (pin "1") (pinfunction "1_1") (pintype "passive"))
      (node (ref "U8") (pin "2") (pinfunction "CRX1_2") (pintype "bidirectional"))
    )
    (net (code "135") (name "Net-(U8-CRX2)") (class "Default")
      (node (ref "R35") (pin "1") (pinfunction "1_1") (pintype "passive"))
      (node (ref "U8") (pin "3") (pinfunction "CRX2_3") (pintype "bidirectional"))
    )
    (net (code "136") (name "Net-(U8-CRX3)") (class "Default")
      (node (ref "R36") (pin "1") (pinfunction "1_1") (pintype "passive"))
      (node (ref "U8") (pin "9") (pinfunction "CRX3_9") (pintype "bidirectional"))
    )
    (net (code "137") (name "Net-(U8-VREG)") (class "Default")
      (node (ref "C27") (pin "1") (pinfunction "1_1") (pintype "bidirectional"))
      (node (ref "C28") (pin "1") (pinfunction "1_1") (pintype "bidirectional"))
      (node (ref "U8") (pin "5") (pinfunction "VREG_5") (pintype "bidirectional"))
    )
    (net (code "138") (name "Net-(U10-PA1)") (class "Default")
      (node (ref "R56") (pin "1") (pinfunction "1_1") (pintype "passive"))
      (node (ref "U10") (pin "4") (pinfunction "PA1_4") (pintype "bidirectional"))
    )
    (net (code "139") (name "Net-(U10-PA6)") (class "Default")
      (node (ref "U10") (pin "16") (pinfunction "PA6_16") (pintype "bidirectional"))
      (node (ref "U9") (pin "G") (pinfunction "G_G") (pintype "passive"))
    )
    (net (code "140") (name "Net-(U11-A0N)") (class "Default")
      (node (ref "U11") (pin "25") (pinfunction "A0N_25") (pintype "bidirectional"))
      (node (ref "U7") (pin "47") (pinfunction "A_Y0N_47") (pintype "bidirectional"))
    )
    (net (code "141") (name "Net-(U11-A0P)") (class "Default")
      (node (ref "U11") (pin "26") (pinfunction "A0P_26") (pintype "bidirectional"))
      (node (ref "U7") (pin "46") (pinfunction "A_Y0P_46") (pintype "bidirectional"))
    )
    (net (code "142") (name "Net-(U11-A1N)") (class "Default")
      (node (ref "U11") (pin "27") (pinfunction "A1N_27") (pintype "bidirectional"))
      (node (ref "U7") (pin "45") (pinfunction "A_Y1N_45") (pintype "bidirectional"))
    )
    (net (code "143") (name "Net-(U11-A1P)") (class "Default")
      (node (ref "U11") (pin "28") (pinfunction "A1P_28") (pintype "bidirectional"))
      (node (ref "U7") (pin "44") (pinfunction "A_Y1P_44") (pintype "bidirectional"))
    )
    (net (code "144") (name "Net-(U11-A2N)") (class "Default")
      (node (ref "U11") (pin "29") (pinfunction "A2N_29") (pintype "bidirectional"))
      (node (ref "U7") (pin "42") (pinfunction "A_Y2N_42") (pintype "bidirectional"))
    )
    (net (code "145") (name "Net-(U11-A2P)") (class "Default")
      (node (ref "U11") (pin "30") (pinfunction "A2P_30") (pintype "bidirectional"))
      (node (ref "U7") (pin "41") (pinfunction "A_Y2P_41") (pintype "bidirectional"))
    )
    (net (code "146") (name "Net-(U11-A3N)") (class "Default")
      (node (ref "U11") (pin "33") (pinfunction "A3N_33") (pintype "bidirectional"))
      (node (ref "U7") (pin "37") (pinfunction "A_Y3N_37") (pintype "bidirectional"))
    )
    (net (code "147") (name "Net-(U11-A3P)") (class "Default")
      (node (ref "U11") (pin "34") (pinfunction "A3P_34") (pintype "bidirectional"))
      (node (ref "U7") (pin "36") (pinfunction "A_Y3P_36") (pintype "bidirectional"))
    )
    (net (code "148") (name "Net-(U11-CLKN)") (class "Default")
      (node (ref "U11") (pin "31") (pinfunction "CLKN_31") (pintype "bidirectional"))
      (node (ref "U7") (pin "39") (pinfunction "A_CLKN_39") (pintype "bidirectional"))
    )
    (net (code "149") (name "Net-(U11-CLKP)") (class "Default")
      (node (ref "U11") (pin "32") (pinfunction "CLKP_32") (pintype "bidirectional"))
      (node (ref "U7") (pin "38") (pinfunction "A_CLKP_38") (pintype "bidirectional"))
    )
    (net (code "150") (name "Net-(U11-SHTDN#)") (class "Default")
      (node (ref "R58") (pin "2") (pinfunction "2_2") (pintype "passive"))
      (node (ref "U11") (pin "37") (pinfunction "SHTDN#_37") (pintype "bidirectional"))
    )
    (net (code "151") (name "Net-(U12-IN1)") (class "Default")
      (node (ref "R15") (pin "2") (pinfunction "2_2") (pintype "passive"))
      (node (ref "U12") (pin "4") (pinfunction "IN1_4") (pintype "bidirectional"))
      (node (ref "U12") (pin "8") (pinfunction "IN2_8") (pintype "bidirectional"))
      (node (ref "U13") (pin "S") (pinfunction "S_S") (pintype "passive"))
    )
    (net (code "152") (name "Net-(U12-NC1)") (class "Default")
      (node (ref "R1") (pin "1") (pinfunction "1_1") (pintype "passive"))
      (node (ref "U12") (pin "5") (pinfunction "NC1_5") (pintype "bidirectional"))
    )
    (net (code "153") (name "Net-(U12-NC2)") (class "Default")
      (node (ref "R8") (pin "1") (pinfunction "1_1") (pintype "passive"))
      (node (ref "U12") (pin "7") (pinfunction "NC2_7") (pintype "bidirectional"))
    )
    (net (code "154") (name "Net-(U12-NO1)") (class "Default")
      (node (ref "R12") (pin "2") (pinfunction "2_2") (pintype "passive"))
      (node (ref "U12") (pin "2") (pinfunction "NO1_2") (pintype "bidirectional"))
    )
    (net (code "155") (name "Net-(U12-NO2)") (class "Default")
      (node (ref "R13") (pin "2") (pinfunction "2_2") (pintype "passive"))
      (node (ref "U12") (pin "10") (pinfunction "NO2_10") (pintype "bidirectional"))
    )
    (net (code "156") (name "Net-(U14-S)") (class "Default")
      (node (ref "F2") (pin "2") (pinfunction "2_2") (pintype "passive"))
      (node (ref "R16") (pin "2") (pinfunction "2_2") (pintype "passive"))
      (node (ref "R19") (pin "1") (pinfunction "1_1") (pintype "passive"))
      (node (ref "U14") (pin "2") (pinfunction "S_2") (pintype "passive"))
      (node (ref "U16") (pin "3") (pinfunction "D_3") (pintype "passive"))
    )
    (net (code "157") (name "Net-(U16-G)") (class "Default")
      (node (ref "R18") (pin "2") (pinfunction "2_2") (pintype "passive"))
      (node (ref "U16") (pin "1") (pinfunction "G_1") (pintype "passive"))
      (node (ref "U17") (pin "3") (pinfunction "D_3") (pintype "passive"))
    )
    (net (code "158") (name "Net-(U21-PROG)") (class "Default")
      (node (ref "R29") (pin "2") (pinfunction "2_2") (pintype "passive"))
      (node (ref "U21") (pin "6") (pinfunction "PROG_6") (pintype "bidirectional"))
    )
    (net (code "159") (name "Net-(U21-THERM)") (class "Default")
      (node (ref "R26") (pin "2") (pinfunction "2_2") (pintype "passive"))
      (node (ref "U21") (pin "8") (pinfunction "THERM_8") (pintype "bidirectional"))
    )
    (net (code "160") (name "Net-(U22-OE)") (class "Default")
      (node (ref "R37") (pin "1") (pinfunction "1_1") (pintype "passive"))
      (node (ref "U22") (pin "8") (pinfunction "OE_8") (pintype "bidirectional"))
      (node (ref "U23") (pin "D") (pinfunction "D_D") (pintype "passive"))
    )
    (net (code "161") (name "Net-(U24-OE)") (class "Default")
      (node (ref "R44") (pin "1") (pinfunction "1_1") (pintype "passive"))
      (node (ref "U24") (pin "8") (pinfunction "OE_8") (pintype "bidirectional"))
    )
    (net (code "162") (name "Net-(U25-OE)") (class "Default")
      (node (ref "R47") (pin "1") (pinfunction "1_1") (pintype "passive"))
      (node (ref "U25") (pin "8") (pinfunction "OE_8") (pintype "bidirectional"))
    )
    (net (code "163") (name "Net-(U26-CAP+)") (class "Default")
      (node (ref "C34") (pin "1") (pinfunction "1_1") (pintype "bidirectional"))
      (node (ref "U26") (pin "6") (pinfunction "CAP+_6") (pintype "bidirectional"))
    )
    (net (code "164") (name "Net-(U26-CAP-)") (class "Default")
      (node (ref "C34") (pin "2") (pinfunction "2_2") (pintype "bidirectional"))
      (node (ref "U26") (pin "3") (pinfunction "CAP-_3") (pintype "bidirectional"))
    )
    (net (code "165") (name "VBATT") (class "Default")
      (node (ref "C10") (pin "1") (pinfunction "1_1") (pintype "bidirectional"))
      (node (ref "C12") (pin "1") (pinfunction "1_1") (pintype "bidirectional"))
      (node (ref "C3") (pin "1") (pinfunction "1_1") (pintype "bidirectional"))
      (node (ref "C7") (pin "2") (pinfunction "2_2") (pintype "bidirectional"))
      (node (ref "C9") (pin "1") (pinfunction "1_1") (pintype "bidirectional"))
      (node (ref "U$1") (pin "J1.1") (pinfunction "VPH_POWER_J1.1") (pintype "bidirectional"))
      (node (ref "U$1") (pin "J1.11") (pinfunction "CDC_VDD_SPKDRV_J1.11") (pintype "bidirectional"))
      (node (ref "U$1") (pin "J1.2") (pinfunction "VPH_POWER_J1.2") (pintype "bidirectional"))
      (node (ref "U$1") (pin "J1.3") (pinfunction "VPH_POWER_J1.3") (pintype "bidirectional"))
      (node (ref "U$1") (pin "J1.4") (pinfunction "VPH_POWER_J1.4") (pintype "bidirectional"))
      (node (ref "U$1") (pin "J1.5") (pinfunction "VPH_POWER_J1.5") (pintype "bidirectional"))
      (node (ref "U$1") (pin "J1.6") (pinfunction "VPH_POWER_J1.6") (pintype "bidirectional"))
      (node (ref "U$1") (pin "J1.7") (pinfunction "VPH_POWER_J1.7") (pintype "bidirectional"))
      (node (ref "U$1") (pin "J1.8") (pinfunction "VPH_POWER_J1.8") (pintype "bidirectional"))
      (node (ref "U$1") (pin "J1.9") (pinfunction "CDC_VDD_SPKDRV_J1.9") (pintype "bidirectional"))
      (node (ref "U18") (pin "1") (pinfunction "VIN_1") (pintype "bidirectional"))
      (node (ref "U18") (pin "3") (pinfunction "EN_3") (pintype "bidirectional"))
      (node (ref "U19") (pin "1") (pinfunction "VIN_1") (pintype "bidirectional"))
      (node (ref "U19") (pin "3") (pinfunction "CTL_3") (pintype "bidirectional"))
      (node (ref "U4") (pin "1") (pinfunction "VIN_1") (pintype "bidirectional"))
      (node (ref "U4") (pin "3") (pinfunction "EN_3") (pintype "bidirectional"))
      (node (ref "U6") (pin "3") (pinfunction "D_3") (pintype "passive"))
    )
    (net (code "166") (name "unconnected-(J1-Pad1)") (class "Default")
      (node (ref "J1") (pin "1") (pinfunction "1_1") (pintype "bidirectional"))
    )
    (net (code "167") (name "unconnected-(J1-Pad2)") (class "Default")
      (node (ref "J1") (pin "2") (pinfunction "2_2") (pintype "bidirectional"))
    )
    (net (code "168") (name "unconnected-(J2-Pad1)") (class "Default")
      (node (ref "J2") (pin "1") (pinfunction "1_1") (pintype "bidirectional"))
    )
    (net (code "169") (name "unconnected-(J2-Pad3)") (class "Default")
      (node (ref "J2") (pin "3") (pinfunction "3_3") (pintype "bidirectional"))
    )
    (net (code "170") (name "unconnected-(J2-Pad5)") (class "Default")
      (node (ref "J2") (pin "5") (pinfunction "5_5") (pintype "bidirectional"))
    )
    (net (code "171") (name "unconnected-(J2-Pad7)") (class "Default")
      (node (ref "J2") (pin "7") (pinfunction "7_7") (pintype "bidirectional"))
    )
    (net (code "172") (name "unconnected-(J2-Pad20)") (class "Default")
      (node (ref "J2") (pin "20") (pinfunction "20_20") (pintype "bidirectional"))
    )
    (net (code "173") (name "unconnected-(J2-Pad22)") (class "Default")
      (node (ref "J2") (pin "22") (pinfunction "22_22") (pintype "bidirectional"))
    )
    (net (code "174") (name "unconnected-(J2-Pad24)") (class "Default")
      (node (ref "J2") (pin "24") (pinfunction "24_24") (pintype "bidirectional"))
    )
    (net (code "175") (name "unconnected-(J2-Pad28)") (class "Default")
      (node (ref "J2") (pin "28") (pinfunction "28_28") (pintype "bidirectional"))
    )
    (net (code "176") (name "unconnected-(J4-Pad3)") (class "Default")
      (node (ref "J4") (pin "3") (pinfunction "3_3") (pintype "bidirectional"))
    )
    (net (code "177") (name "unconnected-(J4-Pad4)") (class "Default")
      (node (ref "J4") (pin "4") (pinfunction "4_4") (pintype "bidirectional"))
    )
    (net (code "178") (name "unconnected-(J4-Pad5)") (class "Default")
      (node (ref "J4") (pin "5") (pinfunction "5_5") (pintype "bidirectional"))
    )
    (net (code "179") (name "unconnected-(J6-Pad1)") (class "Default")
      (node (ref "J6") (pin "1") (pinfunction "1_1") (pintype "bidirectional"))
    )
    (net (code "180") (name "unconnected-(J7-RX1+-PadB11)") (class "Default")
      (node (ref "J7") (pin "B11") (pinfunction "RX1+_B11") (pintype "bidirectional"))
    )
    (net (code "181") (name "unconnected-(J7-RX1--PadB10)") (class "Default")
      (node (ref "J7") (pin "B10") (pinfunction "RX1-_B10") (pintype "bidirectional"))
    )
    (net (code "182") (name "unconnected-(J7-RX2+-PadA11)") (class "Default")
      (node (ref "J7") (pin "A11") (pinfunction "RX2+_A11") (pintype "bidirectional"))
    )
    (net (code "183") (name "unconnected-(J7-RX2--PadA10)") (class "Default")
      (node (ref "J7") (pin "A10") (pinfunction "RX2-_A10") (pintype "bidirectional"))
    )
    (net (code "184") (name "unconnected-(J7-SBU1-PadA8)") (class "Default")
      (node (ref "J7") (pin "A8") (pinfunction "SBU1_A8") (pintype "bidirectional"))
    )
    (net (code "185") (name "unconnected-(J7-SBU2-PadB8)") (class "Default")
      (node (ref "J7") (pin "B8") (pinfunction "SBU2_B8") (pintype "bidirectional"))
    )
    (net (code "186") (name "unconnected-(J7-TX1+-PadA2)") (class "Default")
      (node (ref "J7") (pin "A2") (pinfunction "TX1+_A2") (pintype "bidirectional"))
    )
    (net (code "187") (name "unconnected-(J7-TX1--PadA3)") (class "Default")
      (node (ref "J7") (pin "A3") (pinfunction "TX1-_A3") (pintype "bidirectional"))
    )
    (net (code "188") (name "unconnected-(J7-TX2+-PadB2)") (class "Default")
      (node (ref "J7") (pin "B2") (pinfunction "TX2+_B2") (pintype "bidirectional"))
    )
    (net (code "189") (name "unconnected-(J7-TX2--PadB3)") (class "Default")
      (node (ref "J7") (pin "B3") (pinfunction "TX2-_B3") (pintype "bidirectional"))
    )
    (net (code "190") (name "unconnected-(J8-Pad4)") (class "Default")
      (node (ref "J8") (pin "4") (pinfunction "4_4") (pintype "bidirectional"))
    )
    (net (code "191") (name "unconnected-(J8-Pad5)") (class "Default")
      (node (ref "J8") (pin "5") (pinfunction "5_5") (pintype "bidirectional"))
    )
    (net (code "192") (name "unconnected-(U$1A-APQ_RESIN-PadJ1.89)") (class "Default")
      (node (ref "U$1") (pin "J1.89") (pinfunction "APQ_RESIN_J1.89") (pintype "bidirectional"))
    )
    (net (code "193") (name "unconnected-(U$1A-CDC_HPH_L-PadJ1.23)") (class "Default")
      (node (ref "U$1") (pin "J1.23") (pinfunction "CDC_HPH_L_J1.23") (pintype "bidirectional"))
    )
    (net (code "194") (name "unconnected-(U$1A-CDC_HPH_R-PadJ1.25)") (class "Default")
      (node (ref "U$1") (pin "J1.25") (pinfunction "CDC_HPH_R_J1.25") (pintype "bidirectional"))
    )
    (net (code "195") (name "unconnected-(U$1A-CDC_HPH_REF-PadJ1.27)") (class "Default")
      (node (ref "U$1") (pin "J1.27") (pinfunction "CDC_HPH_REF_J1.27") (pintype "bidirectional"))
    )
    (net (code "196") (name "unconnected-(U$1A-CDC_HS_DET-PadJ1.29)") (class "Default")
      (node (ref "U$1") (pin "J1.29") (pinfunction "CDC_HS_DET_J1.29") (pintype "bidirectional"))
    )
    (net (code "197") (name "unconnected-(U$1A-CDC_MIC1_P-PadJ1.39)") (class "Default")
      (node (ref "U$1") (pin "J1.39") (pinfunction "CDC_MIC1_P_J1.39") (pintype "bidirectional"))
    )
    (net (code "198") (name "unconnected-(U$1A-CDC_MIC2_P-PadJ1.43)") (class "Default")
      (node (ref "U$1") (pin "J1.43") (pinfunction "CDC_MIC2_P_J1.43") (pintype "bidirectional"))
    )
    (net (code "199") (name "unconnected-(U$1A-CDC_MIC_BIAS1-PadJ1.35)") (class "Default")
      (node (ref "U$1") (pin "J1.35") (pinfunction "CDC_MIC_BIAS1_J1.35") (pintype "bidirectional"))
    )
    (net (code "200") (name "unconnected-(U$1A-CDC_MIC_BIAS2-PadJ1.33)") (class "Default")
      (node (ref "U$1") (pin "J1.33") (pinfunction "CDC_MIC_BIAS2_J1.33") (pintype "bidirectional"))
    )
    (net (code "201") (name "unconnected-(U$1A-GPIO9-PadJ1.72)") (class "Default")
      (node (ref "U$1") (pin "J1.72") (pinfunction "GPIO9_J1.72") (pintype "bidirectional"))
    )
    (net (code "202") (name "unconnected-(U$1A-GPIO10-PadJ1.70)") (class "Default")
      (node (ref "U$1") (pin "J1.70") (pinfunction "GPIO10_J1.70") (pintype "bidirectional"))
    )
    (net (code "203") (name "unconnected-(U$1A-GPIO11-PadJ1.74)") (class "Default")
      (node (ref "U$1") (pin "J1.74") (pinfunction "GPIO11_J1.74") (pintype "bidirectional"))
    )
    (net (code "204") (name "unconnected-(U$1A-GPIO26-PadJ1.84)") (class "Default")
      (node (ref "U$1") (pin "J1.84") (pinfunction "GPIO26_J1.84") (pintype "bidirectional"))
    )
    (net (code "205") (name "unconnected-(U$1A-MIPI_CSI0_CLK_N-PadJ1.56)") (class "Default")
      (node (ref "U$1") (pin "J1.56") (pinfunction "MIPI_CSI0_CLK_N_J1.56") (pintype "bidirectional"))
    )
    (net (code "206") (name "unconnected-(U$1A-MIPI_CSI0_CLK_P-PadJ1.58)") (class "Default")
      (node (ref "U$1") (pin "J1.58") (pinfunction "MIPI_CSI0_CLK_P_J1.58") (pintype "bidirectional"))
    )
    (net (code "207") (name "unconnected-(U$1A-MIPI_CSI0_DATA0_N-PadJ1.64)") (class "Default")
      (node (ref "U$1") (pin "J1.64") (pinfunction "MIPI_CSI0_DATA0_N_J1.64") (pintype "bidirectional"))
    )
    (net (code "208") (name "unconnected-(U$1A-MIPI_CSI0_DATA0_P-PadJ1.66)") (class "Default")
      (node (ref "U$1") (pin "J1.66") (pinfunction "MIPI_CSI0_DATA0_P_J1.66") (pintype "bidirectional"))
    )
    (net (code "209") (name "unconnected-(U$1A-MIPI_CSI0_DATA1_N-PadJ1.60)") (class "Default")
      (node (ref "U$1") (pin "J1.60") (pinfunction "MIPI_CSI0_DATA1_N_J1.60") (pintype "bidirectional"))
    )
    (net (code "210") (name "unconnected-(U$1A-MIPI_CSI0_DATA1_P-PadJ1.62)") (class "Default")
      (node (ref "U$1") (pin "J1.62") (pinfunction "MIPI_CSI0_DATA1_P_J1.62") (pintype "bidirectional"))
    )
    (net (code "211") (name "unconnected-(U$1A-MIPI_CSI0_DATA2_N-PadJ1.48)") (class "Default")
      (node (ref "U$1") (pin "J1.48") (pinfunction "MIPI_CSI0_DATA2_N_J1.48") (pintype "bidirectional"))
    )
    (net (code "212") (name "unconnected-(U$1A-MIPI_CSI0_DATA2_P-PadJ1.50)") (class "Default")
      (node (ref "U$1") (pin "J1.50") (pinfunction "MIPI_CSI0_DATA2_P_J1.50") (pintype "bidirectional"))
    )
    (net (code "213") (name "unconnected-(U$1A-MIPI_CSI0_DATA3_N-PadJ1.52)") (class "Default")
      (node (ref "U$1") (pin "J1.52") (pinfunction "MIPI_CSI0_DATA3_N_J1.52") (pintype "bidirectional"))
    )
    (net (code "214") (name "unconnected-(U$1A-MIPI_CSI0_DATA3_P-PadJ1.54)") (class "Default")
      (node (ref "U$1") (pin "J1.54") (pinfunction "MIPI_CSI0_DATA3_P_J1.54") (pintype "bidirectional"))
    )
    (net (code "215") (name "unconnected-(U$1A-SPKR_OUT_N-PadJ1.17)") (class "Default")
      (node (ref "U$1") (pin "J1.17") (pinfunction "SPKR_OUT_N_J1.17") (pintype "bidirectional"))
    )
    (net (code "216") (name "unconnected-(U$1A-SPKR_OUT_N-PadJ1.19)") (class "Default")
      (node (ref "U$1") (pin "J1.19") (pinfunction "SPKR_OUT_N_J1.19") (pintype "bidirectional"))
    )
    (net (code "217") (name "unconnected-(U$1A-SPKR_OUT_P-PadJ1.13)") (class "Default")
      (node (ref "U$1") (pin "J1.13") (pinfunction "SPKR_OUT_P_J1.13") (pintype "bidirectional"))
    )
    (net (code "218") (name "unconnected-(U$1A-SPKR_OUT_P-PadJ1.15)") (class "Default")
      (node (ref "U$1") (pin "J1.15") (pinfunction "SPKR_OUT_P_J1.15") (pintype "bidirectional"))
    )
    (net (code "219") (name "unconnected-(U$1B-BBCLK2-PadJ2.71)") (class "Default")
      (node (ref "U$1") (pin "J2.71") (pinfunction "BBCLK2_J2.71") (pintype "bidirectional"))
    )
    (net (code "220") (name "unconnected-(U$1B-EEPROM_WP-PadJ2.57)") (class "Default")
      (node (ref "U$1") (pin "J2.57") (pinfunction "EEPROM_WP_J2.57") (pintype "bidirectional"))
    )
    (net (code "221") (name "unconnected-(U$1B-FM_RX_ANT-PadJ2.20)") (class "Default")
      (node (ref "U$1") (pin "J2.20") (pinfunction "FM_RX_ANT_J2.20") (pintype "bidirectional"))
    )
    (net (code "222") (name "unconnected-(U$1B-GPIO0-PadJ2.23)") (class "Default")
      (node (ref "U$1") (pin "J2.23") (pinfunction "GPIO0_J2.23") (pintype "bidirectional"))
    )
    (net (code "223") (name "unconnected-(U$1B-GPIO1-PadJ2.27)") (class "Default")
      (node (ref "U$1") (pin "J2.27") (pinfunction "GPIO1_J2.27") (pintype "bidirectional"))
    )
    (net (code "224") (name "unconnected-(U$1B-GPIO2-PadJ2.29)") (class "Default")
      (node (ref "U$1") (pin "J2.29") (pinfunction "GPIO2_J2.29") (pintype "bidirectional"))
    )
    (net (code "225") (name "unconnected-(U$1B-GPIO3-PadJ2.25)") (class "Default")
      (node (ref "U$1") (pin "J2.25") (pinfunction "GPIO3_J2.25") (pintype "bidirectional"))
    )
    (net (code "226") (name "unconnected-(U$1B-GPIO12-PadJ2.73)") (class "Default")
      (node (ref "U$1") (pin "J2.73") (pinfunction "GPIO12_J2.73") (pintype "bidirectional"))
    )
    (net (code "227") (name "unconnected-(U$1B-GPIO13-PadJ2.75)") (class "Default")
      (node (ref "U$1") (pin "J2.75") (pinfunction "GPIO13_J2.75") (pintype "bidirectional"))
    )
    (net (code "228") (name "unconnected-(U$1B-GPIO20-PadJ2.28)") (class "Default")
      (node (ref "U$1") (pin "J2.28") (pinfunction "GPIO20_J2.28") (pintype "bidirectional"))
    )
    (net (code "229") (name "unconnected-(U$1B-GPIO24-PadJ2.40)") (class "Default")
      (node (ref "U$1") (pin "J2.40") (pinfunction "GPIO24_J2.40") (pintype "bidirectional"))
    )
    (net (code "230") (name "unconnected-(U$1B-GPIO25-PadJ2.38)") (class "Default")
      (node (ref "U$1") (pin "J2.38") (pinfunction "GPIO25_J2.38") (pintype "bidirectional"))
    )
    (net (code "231") (name "unconnected-(U$1B-GPIO31-PadJ2.85)") (class "Default")
      (node (ref "U$1") (pin "J2.85") (pinfunction "GPIO31_J2.85") (pintype "bidirectional"))
    )
    (net (code "232") (name "unconnected-(U$1B-GPIO35-PadJ2.83)") (class "Default")
      (node (ref "U$1") (pin "J2.83") (pinfunction "GPIO35_J2.83") (pintype "bidirectional"))
    )
    (net (code "233") (name "unconnected-(U$1B-GPIO38-PadJ2.55)") (class "Default")
      (node (ref "U$1") (pin "J2.55") (pinfunction "GPIO38_J2.55") (pintype "bidirectional"))
    )
    (net (code "234") (name "unconnected-(U$1B-GPIO49-PadJ2.46)") (class "Default")
      (node (ref "U$1") (pin "J2.46") (pinfunction "GPIO49_J2.46") (pintype "bidirectional"))
    )
    (net (code "235") (name "unconnected-(U$1B-GPIO52-PadJ2.44)") (class "Default")
      (node (ref "U$1") (pin "J2.44") (pinfunction "GPIO52_J2.44") (pintype "bidirectional"))
    )
    (net (code "236") (name "unconnected-(U$1B-GPIO62-PadJ2.60)") (class "Default")
      (node (ref "U$1") (pin "J2.60") (pinfunction "GPIO62_J2.60") (pintype "bidirectional"))
    )
    (net (code "237") (name "unconnected-(U$1B-GPIO96-PadJ2.19)") (class "Default")
      (node (ref "U$1") (pin "J2.19") (pinfunction "GPIO96_J2.19") (pintype "bidirectional"))
    )
    (net (code "238") (name "unconnected-(U$1B-GPIO97-PadJ2.81)") (class "Default")
      (node (ref "U$1") (pin "J2.81") (pinfunction "GPIO97_J2.81") (pintype "bidirectional"))
    )
    (net (code "239") (name "unconnected-(U$1B-GPIO98-PadJ2.53)") (class "Default")
      (node (ref "U$1") (pin "J2.53") (pinfunction "GPIO98_J2.53") (pintype "bidirectional"))
    )
    (net (code "240") (name "unconnected-(U$1B-GPIO105-PadJ2.45)") (class "Default")
      (node (ref "U$1") (pin "J2.45") (pinfunction "GPIO105_J2.45") (pintype "bidirectional"))
    )
    (net (code "241") (name "unconnected-(U$1B-GPIO106-PadJ2.39)") (class "Default")
      (node (ref "U$1") (pin "J2.39") (pinfunction "GPIO106_J2.39") (pintype "bidirectional"))
    )
    (net (code "242") (name "unconnected-(U$1B-GPIO107-PadJ2.62)") (class "Default")
      (node (ref "U$1") (pin "J2.62") (pinfunction "GPIO107_J2.62") (pintype "bidirectional"))
    )
    (net (code "243") (name "unconnected-(U$1B-GPIO108-PadJ2.54)") (class "Default")
      (node (ref "U$1") (pin "J2.54") (pinfunction "GPIO108_J2.54") (pintype "bidirectional"))
    )
    (net (code "244") (name "unconnected-(U$1B-GPIO109-PadJ2.58)") (class "Default")
      (node (ref "U$1") (pin "J2.58") (pinfunction "GPIO109_J2.58") (pintype "bidirectional"))
    )
    (net (code "245") (name "unconnected-(U$1B-GPIO110-PadJ2.51)") (class "Default")
      (node (ref "U$1") (pin "J2.51") (pinfunction "GPIO110_J2.51") (pintype "bidirectional"))
    )
    (net (code "246") (name "unconnected-(U$1B-GPIO112-PadJ2.17)") (class "Default")
      (node (ref "U$1") (pin "J2.17") (pinfunction "GPIO112_J2.17") (pintype "bidirectional"))
    )
    (net (code "247") (name "unconnected-(U$1B-GPIO113-PadJ2.47)") (class "Default")
      (node (ref "U$1") (pin "J2.47") (pinfunction "GPIO113_J2.47") (pintype "bidirectional"))
    )
    (net (code "248") (name "unconnected-(U$1B-GPIO114-PadJ2.43)") (class "Default")
      (node (ref "U$1") (pin "J2.43") (pinfunction "GPIO114_J2.43") (pintype "bidirectional"))
    )
    (net (code "249") (name "unconnected-(U$1B-GPIO115-PadJ2.79)") (class "Default")
      (node (ref "U$1") (pin "J2.79") (pinfunction "GPIO115_J2.79") (pintype "bidirectional"))
    )
    (net (code "250") (name "unconnected-(U$1B-GPIO116-PadJ2.41)") (class "Default")
      (node (ref "U$1") (pin "J2.41") (pinfunction "GPIO116_J2.41") (pintype "bidirectional"))
    )
    (net (code "251") (name "unconnected-(U$1B-GPIO117-PadJ2.61)") (class "Default")
      (node (ref "U$1") (pin "J2.61") (pinfunction "GPIO117_J2.61") (pintype "bidirectional"))
    )
    (net (code "252") (name "unconnected-(U$1B-GPIO118-PadJ2.63)") (class "Default")
      (node (ref "U$1") (pin "J2.63") (pinfunction "GPIO118_J2.63") (pintype "bidirectional"))
    )
    (net (code "253") (name "unconnected-(U$1B-GPIO119-PadJ2.59)") (class "Default")
      (node (ref "U$1") (pin "J2.59") (pinfunction "GPIO119_J2.59") (pintype "bidirectional"))
    )
    (net (code "254") (name "unconnected-(U$1B-JTAG_PS_HOLD-PadJ2.80)") (class "Default")
      (node (ref "U$1") (pin "J2.80") (pinfunction "JTAG_PS_HOLD_J2.80") (pintype "bidirectional"))
    )
    (net (code "255") (name "unconnected-(U$1B-JTAG_SRST_N-PadJ2.68)") (class "Default")
      (node (ref "U$1") (pin "J2.68") (pinfunction "JTAG_SRST_N_J2.68") (pintype "bidirectional"))
    )
    (net (code "256") (name "unconnected-(U$1B-JTAG_TCK-PadJ2.72)") (class "Default")
      (node (ref "U$1") (pin "J2.72") (pinfunction "JTAG_TCK_J2.72") (pintype "bidirectional"))
    )
    (net (code "257") (name "unconnected-(U$1B-JTAG_TDI-PadJ2.74)") (class "Default")
      (node (ref "U$1") (pin "J2.74") (pinfunction "JTAG_TDI_J2.74") (pintype "bidirectional"))
    )
    (net (code "258") (name "unconnected-(U$1B-JTAG_TDO-PadJ2.78)") (class "Default")
      (node (ref "U$1") (pin "J2.78") (pinfunction "JTAG_TDO_J2.78") (pintype "bidirectional"))
    )
    (net (code "259") (name "unconnected-(U$1B-JTAG_TMS-PadJ2.70)") (class "Default")
      (node (ref "U$1") (pin "J2.70") (pinfunction "JTAG_TMS_J2.70") (pintype "bidirectional"))
    )
    (net (code "260") (name "unconnected-(U$1B-JTAG_TRST_N-PadJ2.76)") (class "Default")
      (node (ref "U$1") (pin "J2.76") (pinfunction "JTAG_TRST_N_J2.76") (pintype "bidirectional"))
    )
    (net (code "261") (name "unconnected-(U$1B-PM_GPIO1-PadJ2.10)") (class "Default")
      (node (ref "U$1") (pin "J2.10") (pinfunction "PM_GPIO1_J2.10") (pintype "bidirectional"))
    )
    (net (code "262") (name "unconnected-(U$1B-PM_GPIO2-PadJ2.4)") (class "Default")
      (node (ref "U$1") (pin "J2.4") (pinfunction "PM_GPIO2_J2.4") (pintype "bidirectional"))
    )
    (net (code "263") (name "unconnected-(U$1B-PM_GPIO3-PadJ2.16)") (class "Default")
      (node (ref "U$1") (pin "J2.16") (pinfunction "PM_GPIO3_J2.16") (pintype "bidirectional"))
    )
    (net (code "264") (name "unconnected-(U$1B-PM_GPIO4-PadJ2.18)") (class "Default")
      (node (ref "U$1") (pin "J2.18") (pinfunction "PM_GPIO4_J2.18") (pintype "bidirectional"))
    )
    (net (code "265") (name "unconnected-(U$1B-PM_MPP2-PadJ2.8)") (class "Default")
      (node (ref "U$1") (pin "J2.8") (pinfunction "PM_MPP2_J2.8") (pintype "bidirectional"))
    )
    (net (code "266") (name "unconnected-(U$1B-PM_MPP3-PadJ2.2)") (class "Default")
      (node (ref "U$1") (pin "J2.2") (pinfunction "PM_MPP3_J2.2") (pintype "bidirectional"))
    )
    (net (code "267") (name "unconnected-(U$1B-VREG_L12_SDC-PadJ2.13)") (class "Default")
      (node (ref "U$1") (pin "J2.13") (pinfunction "VREG_L12_SDC_J2.13") (pintype "bidirectional"))
    )
    (net (code "268") (name "unconnected-(U1-AUX_CL-Pad7)") (class "Default")
      (node (ref "U1") (pin "7") (pinfunction "AUX_CL_7") (pintype "bidirectional"))
    )
    (net (code "269") (name "unconnected-(U1-AUX_DA-Pad21)") (class "Default")
      (node (ref "U1") (pin "21") (pinfunction "AUX_DA_21") (pintype "bidirectional"))
    )
    (net (code "270") (name "unconnected-(U1-INT1-Pad12)") (class "Default")
      (node (ref "U1") (pin "12") (pinfunction "INT1_12") (pintype "bidirectional"))
    )
    (net (code "271") (name "unconnected-(U7-IRQ-Pad33)") (class "Default")
      (node (ref "U7") (pin "33") (pinfunction "IRQ_33") (pintype "bidirectional"))
    )
    (net (code "272") (name "unconnected-(U8-CTX-Pad10)") (class "Default")
      (node (ref "U8") (pin "10") (pinfunction "CTX_10") (pintype "bidirectional"))
    )
    (net (code "273") (name "unconnected-(U11-CLKPOL-Pad23)") (class "Default")
      (node (ref "U11") (pin "23") (pinfunction "CLKPOL_23") (pintype "bidirectional"))
    )
    (net (code "274") (name "unconnected-(U11-D1-Pad21)") (class "Default")
      (node (ref "U11") (pin "21") (pinfunction "D1_21") (pintype "bidirectional"))
    )
    (net (code "275") (name "unconnected-(U11-D2-Pad20)") (class "Default")
      (node (ref "U11") (pin "20") (pinfunction "D2_20") (pintype "bidirectional"))
    )
    (net (code "276") (name "unconnected-(U11-SLEW-Pad35)") (class "Default")
      (node (ref "U11") (pin "35") (pinfunction "SLEW_35") (pintype "bidirectional"))
    )
    (net (code "277") (name "unconnected-(U21-~{PG}-Pad7)") (class "Default")
      (node (ref "U21") (pin "7") (pinfunction "~{PG}_7") (pintype "bidirectional"))
    )
    (net (code "278") (name "unconnected-(U24-A3-Pad6)") (class "Default")
      (node (ref "U24") (pin "6") (pinfunction "A3_6") (pintype "bidirectional"))
    )
    (net (code "279") (name "unconnected-(U24-B3-Pad9)") (class "Default")
      (node (ref "U24") (pin "9") (pinfunction "B3_9") (pintype "bidirectional"))
    )
    (net (code "280") (name "unconnected-(U25-A3-Pad6)") (class "Default")
      (node (ref "U25") (pin "6") (pinfunction "A3_6") (pintype "bidirectional"))
    )
    (net (code "281") (name "unconnected-(U25-B3-Pad9)") (class "Default")
      (node (ref "U25") (pin "9") (pinfunction "B3_9") (pintype "bidirectional"))
    )
  )
)
